# untitled.net
KiCad netlist of a schematic drawn in EAGLE
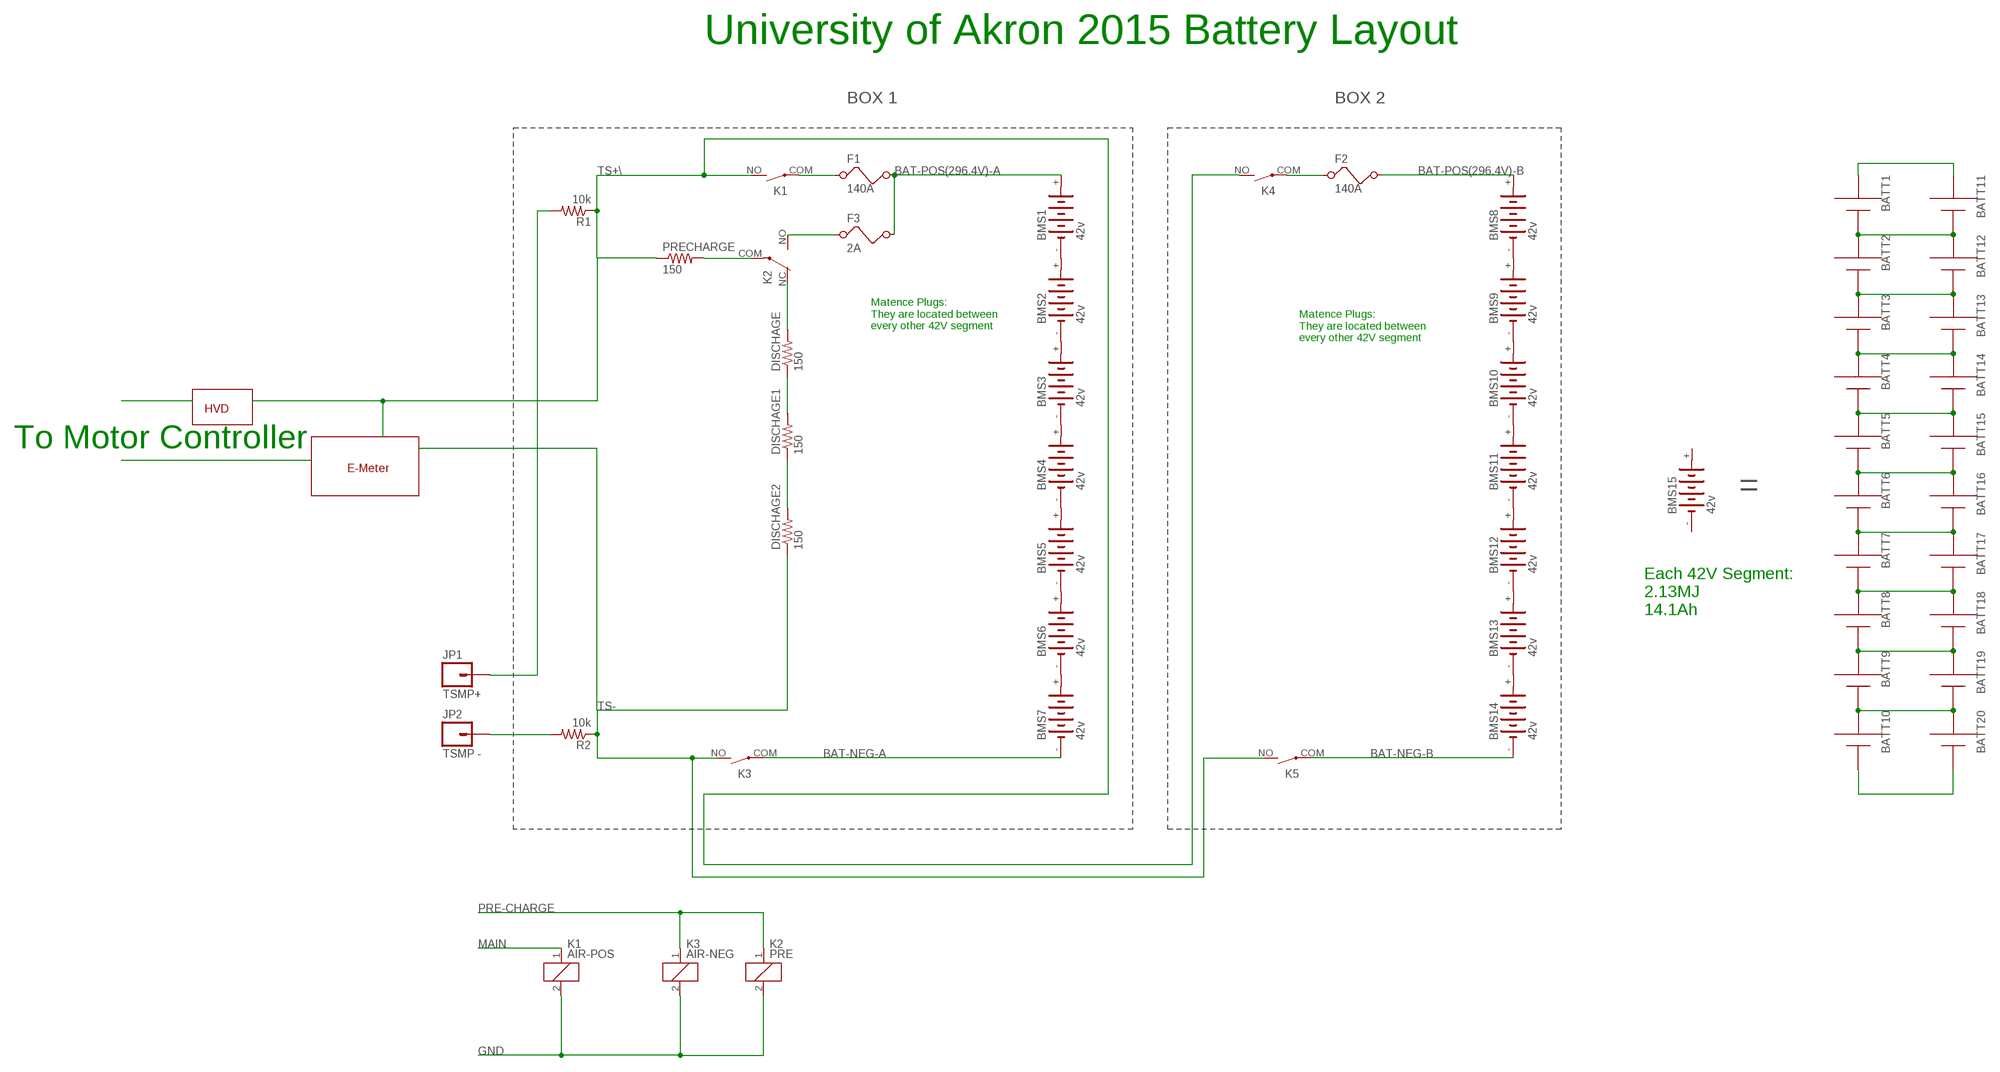
[diagram p0: schematic, sheet 1]
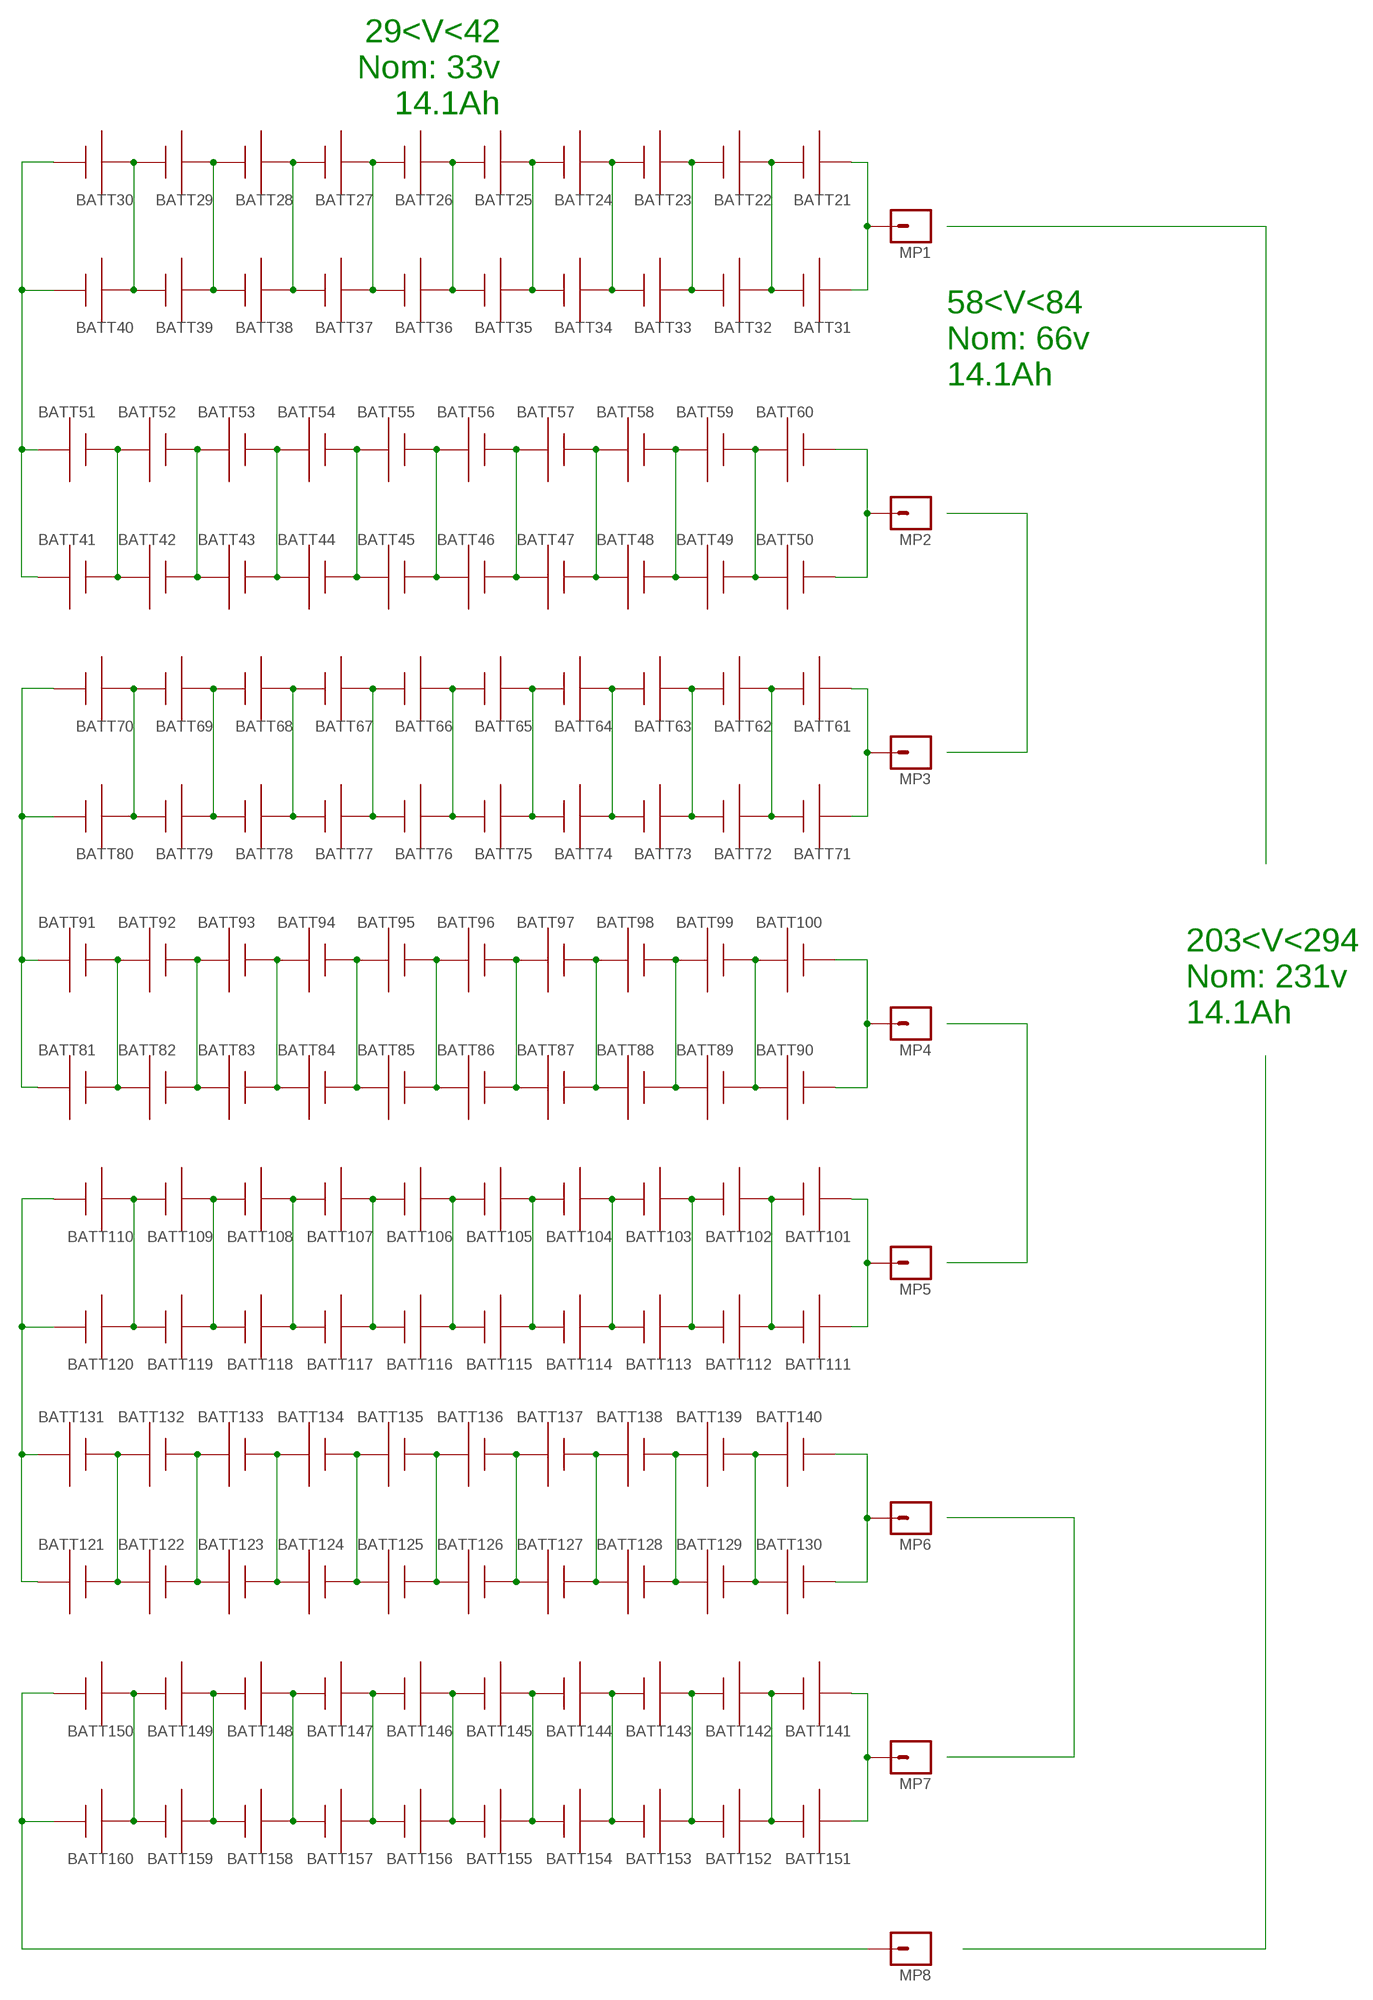
[diagram p1: schematic, sheet 2]
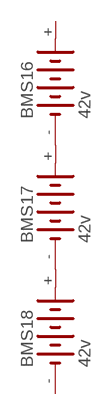
[diagram p2: schematic, sheet 3]

(export (version "E")
  (design (tool "Eeschema 10.0.6"))
  (components
    (comp (ref "BMS16")
      (value "42v")
      (footprint "eagle-import:VST4")
      (libsource (lib "eagle-import") (part "VST4V8"))
    )
    (comp (ref "BMS17")
      (value "42v")
      (footprint "eagle-import:VST4")
      (libsource (lib "eagle-import") (part "VST4V8"))
    )
    (comp (ref "BMS18")
      (value "42v")
      (footprint "eagle-import:VST4")
      (libsource (lib "eagle-import") (part "VST4V8"))
    )
    (comp (ref "BATT1")
      (value "AAA")
      (footprint "eagle-import:12BH412")
      (libsource (lib "eagle-import") (part "AAA"))
    )
    (comp (ref "BATT2")
      (value "AAA")
      (footprint "eagle-import:12BH412")
      (libsource (lib "eagle-import") (part "AAA"))
    )
    (comp (ref "BATT3")
      (value "AAA")
      (footprint "eagle-import:12BH412")
      (libsource (lib "eagle-import") (part "AAA"))
    )
    (comp (ref "BATT4")
      (value "AAA")
      (footprint "eagle-import:12BH412")
      (libsource (lib "eagle-import") (part "AAA"))
    )
    (comp (ref "BATT5")
      (value "AAA")
      (footprint "eagle-import:12BH412")
      (libsource (lib "eagle-import") (part "AAA"))
    )
    (comp (ref "BATT6")
      (value "AAA")
      (footprint "eagle-import:12BH412")
      (libsource (lib "eagle-import") (part "AAA"))
    )
    (comp (ref "BATT7")
      (value "AAA")
      (footprint "eagle-import:12BH412")
      (libsource (lib "eagle-import") (part "AAA"))
    )
    (comp (ref "BATT8")
      (value "AAA")
      (footprint "eagle-import:12BH412")
      (libsource (lib "eagle-import") (part "AAA"))
    )
    (comp (ref "BATT9")
      (value "AAA")
      (footprint "eagle-import:12BH412")
      (libsource (lib "eagle-import") (part "AAA"))
    )
    (comp (ref "BATT10")
      (value "AAA")
      (footprint "eagle-import:12BH412")
      (libsource (lib "eagle-import") (part "AAA"))
    )
    (comp (ref "BATT11")
      (value "AAA")
      (footprint "eagle-import:12BH412")
      (libsource (lib "eagle-import") (part "AAA"))
    )
    (comp (ref "BATT12")
      (value "AAA")
      (footprint "eagle-import:12BH412")
      (libsource (lib "eagle-import") (part "AAA"))
    )
    (comp (ref "BATT13")
      (value "AAA")
      (footprint "eagle-import:12BH412")
      (libsource (lib "eagle-import") (part "AAA"))
    )
    (comp (ref "BATT14")
      (value "AAA")
      (footprint "eagle-import:12BH412")
      (libsource (lib "eagle-import") (part "AAA"))
    )
    (comp (ref "BATT15")
      (value "AAA")
      (footprint "eagle-import:12BH412")
      (libsource (lib "eagle-import") (part "AAA"))
    )
    (comp (ref "BATT16")
      (value "AAA")
      (footprint "eagle-import:12BH412")
      (libsource (lib "eagle-import") (part "AAA"))
    )
    (comp (ref "BATT17")
      (value "AAA")
      (footprint "eagle-import:12BH412")
      (libsource (lib "eagle-import") (part "AAA"))
    )
    (comp (ref "BATT18")
      (value "AAA")
      (footprint "eagle-import:12BH412")
      (libsource (lib "eagle-import") (part "AAA"))
    )
    (comp (ref "BATT19")
      (value "AAA")
      (footprint "eagle-import:12BH412")
      (libsource (lib "eagle-import") (part "AAA"))
    )
    (comp (ref "BATT20")
      (value "AAA")
      (footprint "eagle-import:12BH412")
      (libsource (lib "eagle-import") (part "AAA"))
    )
    (comp (ref "BMS1")
      (value "42v")
      (footprint "eagle-import:VST4")
      (libsource (lib "eagle-import") (part "VST4V8"))
    )
    (comp (ref "BMS2")
      (value "42v")
      (footprint "eagle-import:VST4")
      (libsource (lib "eagle-import") (part "VST4V8"))
    )
    (comp (ref "BMS3")
      (value "42v")
      (footprint "eagle-import:VST4")
      (libsource (lib "eagle-import") (part "VST4V8"))
    )
    (comp (ref "BMS4")
      (value "42v")
      (footprint "eagle-import:VST4")
      (libsource (lib "eagle-import") (part "VST4V8"))
    )
    (comp (ref "BMS5")
      (value "42v")
      (footprint "eagle-import:VST4")
      (libsource (lib "eagle-import") (part "VST4V8"))
    )
    (comp (ref "BMS6")
      (value "42v")
      (footprint "eagle-import:VST4")
      (libsource (lib "eagle-import") (part "VST4V8"))
    )
    (comp (ref "BMS7")
      (value "42v")
      (footprint "eagle-import:VST4")
      (libsource (lib "eagle-import") (part "VST4V8"))
    )
    (comp (ref "BMS8")
      (value "42v")
      (footprint "eagle-import:VST4")
      (libsource (lib "eagle-import") (part "VST4V8"))
    )
    (comp (ref "BMS9")
      (value "42v")
      (footprint "eagle-import:VST4")
      (libsource (lib "eagle-import") (part "VST4V8"))
    )
    (comp (ref "BMS10")
      (value "42v")
      (footprint "eagle-import:VST4")
      (libsource (lib "eagle-import") (part "VST4V8"))
    )
    (comp (ref "BMS11")
      (value "42v")
      (footprint "eagle-import:VST4")
      (libsource (lib "eagle-import") (part "VST4V8"))
    )
    (comp (ref "BMS12")
      (value "42v")
      (footprint "eagle-import:VST4")
      (libsource (lib "eagle-import") (part "VST4V8"))
    )
    (comp (ref "BMS13")
      (value "42v")
      (footprint "eagle-import:VST4")
      (libsource (lib "eagle-import") (part "VST4V8"))
    )
    (comp (ref "BMS14")
      (value "42v")
      (footprint "eagle-import:VST4")
      (libsource (lib "eagle-import") (part "VST4V8"))
    )
    (comp (ref "BMS15")
      (value "42v")
      (footprint "eagle-import:VST4")
      (libsource (lib "eagle-import") (part "VST4V8"))
    )
    (comp (ref "DISCHAGE")
      (value "150")
      (footprint "eagle-import:0603-RES")
      (libsource (lib "eagle-import") (part "2.0KOHM1/10W5%(0603)"))
    )
    (comp (ref "DISCHAGE1")
      (value "150")
      (footprint "eagle-import:0603-RES")
      (libsource (lib "eagle-import") (part "2.0KOHM1/10W5%(0603)"))
    )
    (comp (ref "DISCHAGE2")
      (value "150")
      (footprint "eagle-import:0603-RES")
      (libsource (lib "eagle-import") (part "2.0KOHM1/10W5%(0603)"))
    )
    (comp (ref "F1")
      (value "140A")
      (footprint "eagle-import:FUSE")
      (libsource (lib "eagle-import") (part "FUSE"))
    )
    (comp (ref "F2")
      (value "140A")
      (footprint "eagle-import:FUSE")
      (libsource (lib "eagle-import") (part "FUSE"))
    )
    (comp (ref "F3")
      (value "2A")
      (footprint "eagle-import:FUSE")
      (libsource (lib "eagle-import") (part "FUSE"))
    )
    (comp (ref "JP1")
      (value "TSMP+")
      (footprint "eagle-import:SMTSO-256-ET")
      (libsource (lib "eagle-import") (part "M01-SMTSO-256-ET"))
    )
    (comp (ref "JP2")
      (value "TSMP -")
      (footprint "eagle-import:SMTSO-256-ET")
      (libsource (lib "eagle-import") (part "M01-SMTSO-256-ET"))
    )
    (comp (ref "K1")
      (value "AIR-POS")
      (footprint "eagle-import:APF30212A")
      (libsource (lib "eagle-import") (part "APF30212A"))
    )
    (comp (ref "K2")
      (value "PRE")
      (footprint "eagle-import:APF30212C")
      (libsource (lib "eagle-import") (part "APF30212C"))
    )
    (comp (ref "K3")
      (value "AIR-NEG")
      (footprint "eagle-import:APF30212A")
      (libsource (lib "eagle-import") (part "APF30212A"))
    )
    (comp (ref "K4")
      (value "AIR-POS")
      (footprint "eagle-import:APF30212A")
      (libsource (lib "eagle-import") (part "APF30212A"))
    )
    (comp (ref "K5")
      (value "AIR-NEG")
      (footprint "eagle-import:APF30212A")
      (libsource (lib "eagle-import") (part "APF30212A"))
    )
    (comp (ref "PRECHARGE")
      (value "150")
      (footprint "eagle-import:0603-RES")
      (libsource (lib "eagle-import") (part "2.0KOHM1/10W5%(0603)"))
    )
    (comp (ref "R1")
      (value "10k")
      (footprint "eagle-import:0805")
      (libsource (lib "eagle-import") (part "RESISTOR0805-RES"))
    )
    (comp (ref "R2")
      (value "10k")
      (footprint "eagle-import:0805")
      (libsource (lib "eagle-import") (part "RESISTOR0805-RES"))
    )
    (comp (ref "BATT21")
      (value "AAA")
      (footprint "eagle-import:12BH412")
      (libsource (lib "eagle-import") (part "AAA"))
    )
    (comp (ref "BATT22")
      (value "AAA")
      (footprint "eagle-import:12BH412")
      (libsource (lib "eagle-import") (part "AAA"))
    )
    (comp (ref "BATT23")
      (value "AAA")
      (footprint "eagle-import:12BH412")
      (libsource (lib "eagle-import") (part "AAA"))
    )
    (comp (ref "BATT24")
      (value "AAA")
      (footprint "eagle-import:12BH412")
      (libsource (lib "eagle-import") (part "AAA"))
    )
    (comp (ref "BATT25")
      (value "AAA")
      (footprint "eagle-import:12BH412")
      (libsource (lib "eagle-import") (part "AAA"))
    )
    (comp (ref "BATT26")
      (value "AAA")
      (footprint "eagle-import:12BH412")
      (libsource (lib "eagle-import") (part "AAA"))
    )
    (comp (ref "BATT27")
      (value "AAA")
      (footprint "eagle-import:12BH412")
      (libsource (lib "eagle-import") (part "AAA"))
    )
    (comp (ref "BATT28")
      (value "AAA")
      (footprint "eagle-import:12BH412")
      (libsource (lib "eagle-import") (part "AAA"))
    )
    (comp (ref "BATT29")
      (value "AAA")
      (footprint "eagle-import:12BH412")
      (libsource (lib "eagle-import") (part "AAA"))
    )
    (comp (ref "BATT30")
      (value "AAA")
      (footprint "eagle-import:12BH412")
      (libsource (lib "eagle-import") (part "AAA"))
    )
    (comp (ref "BATT31")
      (value "AAA")
      (footprint "eagle-import:12BH412")
      (libsource (lib "eagle-import") (part "AAA"))
    )
    (comp (ref "BATT32")
      (value "AAA")
      (footprint "eagle-import:12BH412")
      (libsource (lib "eagle-import") (part "AAA"))
    )
    (comp (ref "BATT33")
      (value "AAA")
      (footprint "eagle-import:12BH412")
      (libsource (lib "eagle-import") (part "AAA"))
    )
    (comp (ref "BATT34")
      (value "AAA")
      (footprint "eagle-import:12BH412")
      (libsource (lib "eagle-import") (part "AAA"))
    )
    (comp (ref "BATT35")
      (value "AAA")
      (footprint "eagle-import:12BH412")
      (libsource (lib "eagle-import") (part "AAA"))
    )
    (comp (ref "BATT36")
      (value "AAA")
      (footprint "eagle-import:12BH412")
      (libsource (lib "eagle-import") (part "AAA"))
    )
    (comp (ref "BATT37")
      (value "AAA")
      (footprint "eagle-import:12BH412")
      (libsource (lib "eagle-import") (part "AAA"))
    )
    (comp (ref "BATT38")
      (value "AAA")
      (footprint "eagle-import:12BH412")
      (libsource (lib "eagle-import") (part "AAA"))
    )
    (comp (ref "BATT39")
      (value "AAA")
      (footprint "eagle-import:12BH412")
      (libsource (lib "eagle-import") (part "AAA"))
    )
    (comp (ref "BATT40")
      (value "AAA")
      (footprint "eagle-import:12BH412")
      (libsource (lib "eagle-import") (part "AAA"))
    )
    (comp (ref "BATT41")
      (value "AAA")
      (footprint "eagle-import:12BH412")
      (libsource (lib "eagle-import") (part "AAA"))
    )
    (comp (ref "BATT42")
      (value "AAA")
      (footprint "eagle-import:12BH412")
      (libsource (lib "eagle-import") (part "AAA"))
    )
    (comp (ref "BATT43")
      (value "AAA")
      (footprint "eagle-import:12BH412")
      (libsource (lib "eagle-import") (part "AAA"))
    )
    (comp (ref "BATT44")
      (value "AAA")
      (footprint "eagle-import:12BH412")
      (libsource (lib "eagle-import") (part "AAA"))
    )
    (comp (ref "BATT45")
      (value "AAA")
      (footprint "eagle-import:12BH412")
      (libsource (lib "eagle-import") (part "AAA"))
    )
    (comp (ref "BATT46")
      (value "AAA")
      (footprint "eagle-import:12BH412")
      (libsource (lib "eagle-import") (part "AAA"))
    )
    (comp (ref "BATT47")
      (value "AAA")
      (footprint "eagle-import:12BH412")
      (libsource (lib "eagle-import") (part "AAA"))
    )
    (comp (ref "BATT48")
      (value "AAA")
      (footprint "eagle-import:12BH412")
      (libsource (lib "eagle-import") (part "AAA"))
    )
    (comp (ref "BATT49")
      (value "AAA")
      (footprint "eagle-import:12BH412")
      (libsource (lib "eagle-import") (part "AAA"))
    )
    (comp (ref "BATT50")
      (value "AAA")
      (footprint "eagle-import:12BH412")
      (libsource (lib "eagle-import") (part "AAA"))
    )
    (comp (ref "BATT51")
      (value "AAA")
      (footprint "eagle-import:12BH412")
      (libsource (lib "eagle-import") (part "AAA"))
    )
    (comp (ref "BATT52")
      (value "AAA")
      (footprint "eagle-import:12BH412")
      (libsource (lib "eagle-import") (part "AAA"))
    )
    (comp (ref "BATT53")
      (value "AAA")
      (footprint "eagle-import:12BH412")
      (libsource (lib "eagle-import") (part "AAA"))
    )
    (comp (ref "BATT54")
      (value "AAA")
      (footprint "eagle-import:12BH412")
      (libsource (lib "eagle-import") (part "AAA"))
    )
    (comp (ref "BATT55")
      (value "AAA")
      (footprint "eagle-import:12BH412")
      (libsource (lib "eagle-import") (part "AAA"))
    )
    (comp (ref "BATT56")
      (value "AAA")
      (footprint "eagle-import:12BH412")
      (libsource (lib "eagle-import") (part "AAA"))
    )
    (comp (ref "BATT57")
      (value "AAA")
      (footprint "eagle-import:12BH412")
      (libsource (lib "eagle-import") (part "AAA"))
    )
    (comp (ref "BATT58")
      (value "AAA")
      (footprint "eagle-import:12BH412")
      (libsource (lib "eagle-import") (part "AAA"))
    )
    (comp (ref "BATT59")
      (value "AAA")
      (footprint "eagle-import:12BH412")
      (libsource (lib "eagle-import") (part "AAA"))
    )
    (comp (ref "BATT60")
      (value "AAA")
      (footprint "eagle-import:12BH412")
      (libsource (lib "eagle-import") (part "AAA"))
    )
    (comp (ref "BATT61")
      (value "AAA")
      (footprint "eagle-import:12BH412")
      (libsource (lib "eagle-import") (part "AAA"))
    )
    (comp (ref "BATT62")
      (value "AAA")
      (footprint "eagle-import:12BH412")
      (libsource (lib "eagle-import") (part "AAA"))
    )
    (comp (ref "BATT63")
      (value "AAA")
      (footprint "eagle-import:12BH412")
      (libsource (lib "eagle-import") (part "AAA"))
    )
    (comp (ref "BATT64")
      (value "AAA")
      (footprint "eagle-import:12BH412")
      (libsource (lib "eagle-import") (part "AAA"))
    )
    (comp (ref "BATT65")
      (value "AAA")
      (footprint "eagle-import:12BH412")
      (libsource (lib "eagle-import") (part "AAA"))
    )
    (comp (ref "BATT66")
      (value "AAA")
      (footprint "eagle-import:12BH412")
      (libsource (lib "eagle-import") (part "AAA"))
    )
    (comp (ref "BATT67")
      (value "AAA")
      (footprint "eagle-import:12BH412")
      (libsource (lib "eagle-import") (part "AAA"))
    )
    (comp (ref "BATT68")
      (value "AAA")
      (footprint "eagle-import:12BH412")
      (libsource (lib "eagle-import") (part "AAA"))
    )
    (comp (ref "BATT69")
      (value "AAA")
      (footprint "eagle-import:12BH412")
      (libsource (lib "eagle-import") (part "AAA"))
    )
    (comp (ref "BATT70")
      (value "AAA")
      (footprint "eagle-import:12BH412")
      (libsource (lib "eagle-import") (part "AAA"))
    )
    (comp (ref "BATT71")
      (value "AAA")
      (footprint "eagle-import:12BH412")
      (libsource (lib "eagle-import") (part "AAA"))
    )
    (comp (ref "BATT72")
      (value "AAA")
      (footprint "eagle-import:12BH412")
      (libsource (lib "eagle-import") (part "AAA"))
    )
    (comp (ref "BATT73")
      (value "AAA")
      (footprint "eagle-import:12BH412")
      (libsource (lib "eagle-import") (part "AAA"))
    )
    (comp (ref "BATT74")
      (value "AAA")
      (footprint "eagle-import:12BH412")
      (libsource (lib "eagle-import") (part "AAA"))
    )
    (comp (ref "BATT75")
      (value "AAA")
      (footprint "eagle-import:12BH412")
      (libsource (lib "eagle-import") (part "AAA"))
    )
    (comp (ref "BATT76")
      (value "AAA")
      (footprint "eagle-import:12BH412")
      (libsource (lib "eagle-import") (part "AAA"))
    )
    (comp (ref "BATT77")
      (value "AAA")
      (footprint "eagle-import:12BH412")
      (libsource (lib "eagle-import") (part "AAA"))
    )
    (comp (ref "BATT78")
      (value "AAA")
      (footprint "eagle-import:12BH412")
      (libsource (lib "eagle-import") (part "AAA"))
    )
    (comp (ref "BATT79")
      (value "AAA")
      (footprint "eagle-import:12BH412")
      (libsource (lib "eagle-import") (part "AAA"))
    )
    (comp (ref "BATT80")
      (value "AAA")
      (footprint "eagle-import:12BH412")
      (libsource (lib "eagle-import") (part "AAA"))
    )
    (comp (ref "BATT81")
      (value "AAA")
      (footprint "eagle-import:12BH412")
      (libsource (lib "eagle-import") (part "AAA"))
    )
    (comp (ref "BATT82")
      (value "AAA")
      (footprint "eagle-import:12BH412")
      (libsource (lib "eagle-import") (part "AAA"))
    )
    (comp (ref "BATT83")
      (value "AAA")
      (footprint "eagle-import:12BH412")
      (libsource (lib "eagle-import") (part "AAA"))
    )
    (comp (ref "BATT84")
      (value "AAA")
      (footprint "eagle-import:12BH412")
      (libsource (lib "eagle-import") (part "AAA"))
    )
    (comp (ref "BATT85")
      (value "AAA")
      (footprint "eagle-import:12BH412")
      (libsource (lib "eagle-import") (part "AAA"))
    )
    (comp (ref "BATT86")
      (value "AAA")
      (footprint "eagle-import:12BH412")
      (libsource (lib "eagle-import") (part "AAA"))
    )
    (comp (ref "BATT87")
      (value "AAA")
      (footprint "eagle-import:12BH412")
      (libsource (lib "eagle-import") (part "AAA"))
    )
    (comp (ref "BATT88")
      (value "AAA")
      (footprint "eagle-import:12BH412")
      (libsource (lib "eagle-import") (part "AAA"))
    )
    (comp (ref "BATT89")
      (value "AAA")
      (footprint "eagle-import:12BH412")
      (libsource (lib "eagle-import") (part "AAA"))
    )
    (comp (ref "BATT90")
      (value "AAA")
      (footprint "eagle-import:12BH412")
      (libsource (lib "eagle-import") (part "AAA"))
    )
    (comp (ref "BATT91")
      (value "AAA")
      (footprint "eagle-import:12BH412")
      (libsource (lib "eagle-import") (part "AAA"))
    )
    (comp (ref "BATT92")
      (value "AAA")
      (footprint "eagle-import:12BH412")
      (libsource (lib "eagle-import") (part "AAA"))
    )
    (comp (ref "BATT93")
      (value "AAA")
      (footprint "eagle-import:12BH412")
      (libsource (lib "eagle-import") (part "AAA"))
    )
    (comp (ref "BATT94")
      (value "AAA")
      (footprint "eagle-import:12BH412")
      (libsource (lib "eagle-import") (part "AAA"))
    )
    (comp (ref "BATT95")
      (value "AAA")
      (footprint "eagle-import:12BH412")
      (libsource (lib "eagle-import") (part "AAA"))
    )
    (comp (ref "BATT96")
      (value "AAA")
      (footprint "eagle-import:12BH412")
      (libsource (lib "eagle-import") (part "AAA"))
    )
    (comp (ref "BATT97")
      (value "AAA")
      (footprint "eagle-import:12BH412")
      (libsource (lib "eagle-import") (part "AAA"))
    )
    (comp (ref "BATT98")
      (value "AAA")
      (footprint "eagle-import:12BH412")
      (libsource (lib "eagle-import") (part "AAA"))
    )
    (comp (ref "BATT99")
      (value "AAA")
      (footprint "eagle-import:12BH412")
      (libsource (lib "eagle-import") (part "AAA"))
    )
    (comp (ref "BATT100")
      (value "AAA")
      (footprint "eagle-import:12BH412")
      (libsource (lib "eagle-import") (part "AAA"))
    )
    (comp (ref "BATT101")
      (value "AAA")
      (footprint "eagle-import:12BH412")
      (libsource (lib "eagle-import") (part "AAA"))
    )
    (comp (ref "BATT102")
      (value "AAA")
      (footprint "eagle-import:12BH412")
      (libsource (lib "eagle-import") (part "AAA"))
    )
    (comp (ref "BATT103")
      (value "AAA")
      (footprint "eagle-import:12BH412")
      (libsource (lib "eagle-import") (part "AAA"))
    )
    (comp (ref "BATT104")
      (value "AAA")
      (footprint "eagle-import:12BH412")
      (libsource (lib "eagle-import") (part "AAA"))
    )
    (comp (ref "BATT105")
      (value "AAA")
      (footprint "eagle-import:12BH412")
      (libsource (lib "eagle-import") (part "AAA"))
    )
    (comp (ref "BATT106")
      (value "AAA")
      (footprint "eagle-import:12BH412")
      (libsource (lib "eagle-import") (part "AAA"))
    )
    (comp (ref "BATT107")
      (value "AAA")
      (footprint "eagle-import:12BH412")
      (libsource (lib "eagle-import") (part "AAA"))
    )
    (comp (ref "BATT108")
      (value "AAA")
      (footprint "eagle-import:12BH412")
      (libsource (lib "eagle-import") (part "AAA"))
    )
    (comp (ref "BATT109")
      (value "AAA")
      (footprint "eagle-import:12BH412")
      (libsource (lib "eagle-import") (part "AAA"))
    )
    (comp (ref "BATT110")
      (value "AAA")
      (footprint "eagle-import:12BH412")
      (libsource (lib "eagle-import") (part "AAA"))
    )
    (comp (ref "BATT111")
      (value "AAA")
      (footprint "eagle-import:12BH412")
      (libsource (lib "eagle-import") (part "AAA"))
    )
    (comp (ref "BATT112")
      (value "AAA")
      (footprint "eagle-import:12BH412")
      (libsource (lib "eagle-import") (part "AAA"))
    )
    (comp (ref "BATT113")
      (value "AAA")
      (footprint "eagle-import:12BH412")
      (libsource (lib "eagle-import") (part "AAA"))
    )
    (comp (ref "BATT114")
      (value "AAA")
      (footprint "eagle-import:12BH412")
      (libsource (lib "eagle-import") (part "AAA"))
    )
    (comp (ref "BATT115")
      (value "AAA")
      (footprint "eagle-import:12BH412")
      (libsource (lib "eagle-import") (part "AAA"))
    )
    (comp (ref "BATT116")
      (value "AAA")
      (footprint "eagle-import:12BH412")
      (libsource (lib "eagle-import") (part "AAA"))
    )
    (comp (ref "BATT117")
      (value "AAA")
      (footprint "eagle-import:12BH412")
      (libsource (lib "eagle-import") (part "AAA"))
    )
    (comp (ref "BATT118")
      (value "AAA")
      (footprint "eagle-import:12BH412")
      (libsource (lib "eagle-import") (part "AAA"))
    )
    (comp (ref "BATT119")
      (value "AAA")
      (footprint "eagle-import:12BH412")
      (libsource (lib "eagle-import") (part "AAA"))
    )
    (comp (ref "BATT120")
      (value "AAA")
      (footprint "eagle-import:12BH412")
      (libsource (lib "eagle-import") (part "AAA"))
    )
    (comp (ref "BATT121")
      (value "AAA")
      (footprint "eagle-import:12BH412")
      (libsource (lib "eagle-import") (part "AAA"))
    )
    (comp (ref "BATT122")
      (value "AAA")
      (footprint "eagle-import:12BH412")
      (libsource (lib "eagle-import") (part "AAA"))
    )
    (comp (ref "BATT123")
      (value "AAA")
      (footprint "eagle-import:12BH412")
      (libsource (lib "eagle-import") (part "AAA"))
    )
    (comp (ref "BATT124")
      (value "AAA")
      (footprint "eagle-import:12BH412")
      (libsource (lib "eagle-import") (part "AAA"))
    )
    (comp (ref "BATT125")
      (value "AAA")
      (footprint "eagle-import:12BH412")
      (libsource (lib "eagle-import") (part "AAA"))
    )
    (comp (ref "BATT126")
      (value "AAA")
      (footprint "eagle-import:12BH412")
      (libsource (lib "eagle-import") (part "AAA"))
    )
    (comp (ref "BATT127")
      (value "AAA")
      (footprint "eagle-import:12BH412")
      (libsource (lib "eagle-import") (part "AAA"))
    )
    (comp (ref "BATT128")
      (value "AAA")
      (footprint "eagle-import:12BH412")
      (libsource (lib "eagle-import") (part "AAA"))
    )
    (comp (ref "BATT129")
      (value "AAA")
      (footprint "eagle-import:12BH412")
      (libsource (lib "eagle-import") (part "AAA"))
    )
    (comp (ref "BATT130")
      (value "AAA")
      (footprint "eagle-import:12BH412")
      (libsource (lib "eagle-import") (part "AAA"))
    )
    (comp (ref "BATT131")
      (value "AAA")
      (footprint "eagle-import:12BH412")
      (libsource (lib "eagle-import") (part "AAA"))
    )
    (comp (ref "BATT132")
      (value "AAA")
      (footprint "eagle-import:12BH412")
      (libsource (lib "eagle-import") (part "AAA"))
    )
    (comp (ref "BATT133")
      (value "AAA")
      (footprint "eagle-import:12BH412")
      (libsource (lib "eagle-import") (part "AAA"))
    )
    (comp (ref "BATT134")
      (value "AAA")
      (footprint "eagle-import:12BH412")
      (libsource (lib "eagle-import") (part "AAA"))
    )
    (comp (ref "BATT135")
      (value "AAA")
      (footprint "eagle-import:12BH412")
      (libsource (lib "eagle-import") (part "AAA"))
    )
    (comp (ref "BATT136")
      (value "AAA")
      (footprint "eagle-import:12BH412")
      (libsource (lib "eagle-import") (part "AAA"))
    )
    (comp (ref "BATT137")
      (value "AAA")
      (footprint "eagle-import:12BH412")
      (libsource (lib "eagle-import") (part "AAA"))
    )
    (comp (ref "BATT138")
      (value "AAA")
      (footprint "eagle-import:12BH412")
      (libsource (lib "eagle-import") (part "AAA"))
    )
    (comp (ref "BATT139")
      (value "AAA")
      (footprint "eagle-import:12BH412")
      (libsource (lib "eagle-import") (part "AAA"))
    )
    (comp (ref "BATT140")
      (value "AAA")
      (footprint "eagle-import:12BH412")
      (libsource (lib "eagle-import") (part "AAA"))
    )
    (comp (ref "BATT141")
      (value "AAA")
      (footprint "eagle-import:12BH412")
      (libsource (lib "eagle-import") (part "AAA"))
    )
    (comp (ref "BATT142")
      (value "AAA")
      (footprint "eagle-import:12BH412")
      (libsource (lib "eagle-import") (part "AAA"))
    )
    (comp (ref "BATT143")
      (value "AAA")
      (footprint "eagle-import:12BH412")
      (libsource (lib "eagle-import") (part "AAA"))
    )
    (comp (ref "BATT144")
      (value "AAA")
      (footprint "eagle-import:12BH412")
      (libsource (lib "eagle-import") (part "AAA"))
    )
    (comp (ref "BATT145")
      (value "AAA")
      (footprint "eagle-import:12BH412")
      (libsource (lib "eagle-import") (part "AAA"))
    )
    (comp (ref "BATT146")
      (value "AAA")
      (footprint "eagle-import:12BH412")
      (libsource (lib "eagle-import") (part "AAA"))
    )
    (comp (ref "BATT147")
      (value "AAA")
      (footprint "eagle-import:12BH412")
      (libsource (lib "eagle-import") (part "AAA"))
    )
    (comp (ref "BATT148")
      (value "AAA")
      (footprint "eagle-import:12BH412")
      (libsource (lib "eagle-import") (part "AAA"))
    )
    (comp (ref "BATT149")
      (value "AAA")
      (footprint "eagle-import:12BH412")
      (libsource (lib "eagle-import") (part "AAA"))
    )
    (comp (ref "BATT150")
      (value "AAA")
      (footprint "eagle-import:12BH412")
      (libsource (lib "eagle-import") (part "AAA"))
    )
    (comp (ref "BATT151")
      (value "AAA")
      (footprint "eagle-import:12BH412")
      (libsource (lib "eagle-import") (part "AAA"))
    )
    (comp (ref "BATT152")
      (value "AAA")
      (footprint "eagle-import:12BH412")
      (libsource (lib "eagle-import") (part "AAA"))
    )
    (comp (ref "BATT153")
      (value "AAA")
      (footprint "eagle-import:12BH412")
      (libsource (lib "eagle-import") (part "AAA"))
    )
    (comp (ref "BATT154")
      (value "AAA")
      (footprint "eagle-import:12BH412")
      (libsource (lib "eagle-import") (part "AAA"))
    )
    (comp (ref "BATT155")
      (value "AAA")
      (footprint "eagle-import:12BH412")
      (libsource (lib "eagle-import") (part "AAA"))
    )
    (comp (ref "BATT156")
      (value "AAA")
      (footprint "eagle-import:12BH412")
      (libsource (lib "eagle-import") (part "AAA"))
    )
    (comp (ref "BATT157")
      (value "AAA")
      (footprint "eagle-import:12BH412")
      (libsource (lib "eagle-import") (part "AAA"))
    )
    (comp (ref "BATT158")
      (value "AAA")
      (footprint "eagle-import:12BH412")
      (libsource (lib "eagle-import") (part "AAA"))
    )
    (comp (ref "BATT159")
      (value "AAA")
      (footprint "eagle-import:12BH412")
      (libsource (lib "eagle-import") (part "AAA"))
    )
    (comp (ref "BATT160")
      (value "AAA")
      (footprint "eagle-import:12BH412")
      (libsource (lib "eagle-import") (part "AAA"))
    )
    (comp (ref "MP1")
      (value "M01POGOPIN_HOLE_0.58")
      (footprint "eagle-import:1X01_POGOPIN_HOLE_0.58")
      (libsource (lib "eagle-import") (part "M01POGOPIN_HOLE_0.58"))
    )
    (comp (ref "MP2")
      (value "M01POGOPIN_HOLE_0.58")
      (footprint "eagle-import:1X01_POGOPIN_HOLE_0.58")
      (libsource (lib "eagle-import") (part "M01POGOPIN_HOLE_0.58"))
    )
    (comp (ref "MP3")
      (value "M01POGOPIN_HOLE_0.58")
      (footprint "eagle-import:1X01_POGOPIN_HOLE_0.58")
      (libsource (lib "eagle-import") (part "M01POGOPIN_HOLE_0.58"))
    )
    (comp (ref "MP4")
      (value "M01POGOPIN_HOLE_0.58")
      (footprint "eagle-import:1X01_POGOPIN_HOLE_0.58")
      (libsource (lib "eagle-import") (part "M01POGOPIN_HOLE_0.58"))
    )
    (comp (ref "MP5")
      (value "M01POGOPIN_HOLE_0.58")
      (footprint "eagle-import:1X01_POGOPIN_HOLE_0.58")
      (libsource (lib "eagle-import") (part "M01POGOPIN_HOLE_0.58"))
    )
    (comp (ref "MP6")
      (value "M01POGOPIN_HOLE_0.58")
      (footprint "eagle-import:1X01_POGOPIN_HOLE_0.58")
      (libsource (lib "eagle-import") (part "M01POGOPIN_HOLE_0.58"))
    )
    (comp (ref "MP7")
      (value "M01POGOPIN_HOLE_0.58")
      (footprint "eagle-import:1X01_POGOPIN_HOLE_0.58")
      (libsource (lib "eagle-import") (part "M01POGOPIN_HOLE_0.58"))
    )
    (comp (ref "MP8")
      (value "M01POGOPIN_HOLE_0.58")
      (footprint "eagle-import:1X01_POGOPIN_HOLE_0.58")
      (libsource (lib "eagle-import") (part "M01POGOPIN_HOLE_0.58"))
    )
  )
  (nets
    (net (code "1") (name "BAT-NEG-A") (class "Default")
      (node (ref "BMS7") (pin "-") (pinfunction "-_-") (pintype "passive"))
      (node (ref "K3") (pin "COM") (pinfunction "P_COM") (pintype "passive"))
    )
    (net (code "2") (name "BAT-NEG-B") (class "Default")
      (node (ref "BMS14") (pin "-") (pinfunction "-_-") (pintype "passive"))
      (node (ref "K5") (pin "COM") (pinfunction "P_COM") (pintype "passive"))
    )
    (net (code "3") (name "BAT-POS(296.4V)-A") (class "Default")
      (node (ref "BMS1") (pin "+") (pinfunction "+_+") (pintype "passive"))
      (node (ref "F1") (pin "2") (pinfunction "2_2") (pintype "passive"))
      (node (ref "F3") (pin "2") (pinfunction "2_2") (pintype "passive"))
    )
    (net (code "4") (name "BAT-POS(296.4V)-B") (class "Default")
      (node (ref "BMS8") (pin "+") (pinfunction "+_+") (pintype "passive"))
      (node (ref "F2") (pin "2") (pinfunction "2_2") (pintype "passive"))
    )
    (net (code "5") (name "GND") (class "Default")
      (node (ref "K1") (pin "2") (pinfunction "2_2") (pintype "passive"))
      (node (ref "K2") (pin "2") (pinfunction "2_2") (pintype "passive"))
      (node (ref "K3") (pin "2") (pinfunction "2_2") (pintype "passive"))
    )
    (net (code "6") (name "MAIN") (class "Default")
      (node (ref "K1") (pin "1") (pinfunction "1_1") (pintype "passive"))
    )
    (net (code "7") (name "Net-(BATT1-Pad+)") (class "Default")
      (node (ref "BATT1") (pin "+") (pinfunction "+_+") (pintype "bidirectional"))
      (node (ref "BATT11") (pin "+") (pinfunction "+_+") (pintype "bidirectional"))
      (node (ref "BATT12") (pin "-") (pinfunction "-_-") (pintype "bidirectional"))
      (node (ref "BATT2") (pin "-") (pinfunction "-_-") (pintype "bidirectional"))
    )
    (net (code "8") (name "Net-(BATT1-Pad-)") (class "Default")
      (node (ref "BATT1") (pin "-") (pinfunction "-_-") (pintype "bidirectional"))
      (node (ref "BATT11") (pin "-") (pinfunction "-_-") (pintype "bidirectional"))
    )
    (net (code "9") (name "Net-(BATT10-Pad+)") (class "Default")
      (node (ref "BATT10") (pin "+") (pinfunction "+_+") (pintype "bidirectional"))
      (node (ref "BATT20") (pin "+") (pinfunction "+_+") (pintype "bidirectional"))
    )
    (net (code "10") (name "Net-(BATT10-Pad-)") (class "Default")
      (node (ref "BATT10") (pin "-") (pinfunction "-_-") (pintype "bidirectional"))
      (node (ref "BATT19") (pin "+") (pinfunction "+_+") (pintype "bidirectional"))
      (node (ref "BATT20") (pin "-") (pinfunction "-_-") (pintype "bidirectional"))
      (node (ref "BATT9") (pin "+") (pinfunction "+_+") (pintype "bidirectional"))
    )
    (net (code "11") (name "Net-(BATT12-Pad+)") (class "Default")
      (node (ref "BATT12") (pin "+") (pinfunction "+_+") (pintype "bidirectional"))
      (node (ref "BATT13") (pin "-") (pinfunction "-_-") (pintype "bidirectional"))
      (node (ref "BATT2") (pin "+") (pinfunction "+_+") (pintype "bidirectional"))
      (node (ref "BATT3") (pin "-") (pinfunction "-_-") (pintype "bidirectional"))
    )
    (net (code "12") (name "Net-(BATT13-Pad+)") (class "Default")
      (node (ref "BATT13") (pin "+") (pinfunction "+_+") (pintype "bidirectional"))
      (node (ref "BATT14") (pin "-") (pinfunction "-_-") (pintype "bidirectional"))
      (node (ref "BATT3") (pin "+") (pinfunction "+_+") (pintype "bidirectional"))
      (node (ref "BATT4") (pin "-") (pinfunction "-_-") (pintype "bidirectional"))
    )
    (net (code "13") (name "Net-(BATT14-Pad+)") (class "Default")
      (node (ref "BATT14") (pin "+") (pinfunction "+_+") (pintype "bidirectional"))
      (node (ref "BATT15") (pin "-") (pinfunction "-_-") (pintype "bidirectional"))
      (node (ref "BATT4") (pin "+") (pinfunction "+_+") (pintype "bidirectional"))
      (node (ref "BATT5") (pin "-") (pinfunction "-_-") (pintype "bidirectional"))
    )
    (net (code "14") (name "Net-(BATT15-Pad+)") (class "Default")
      (node (ref "BATT15") (pin "+") (pinfunction "+_+") (pintype "bidirectional"))
      (node (ref "BATT16") (pin "-") (pinfunction "-_-") (pintype "bidirectional"))
      (node (ref "BATT5") (pin "+") (pinfunction "+_+") (pintype "bidirectional"))
      (node (ref "BATT6") (pin "-") (pinfunction "-_-") (pintype "bidirectional"))
    )
    (net (code "15") (name "Net-(BATT16-Pad+)") (class "Default")
      (node (ref "BATT16") (pin "+") (pinfunction "+_+") (pintype "bidirectional"))
      (node (ref "BATT17") (pin "-") (pinfunction "-_-") (pintype "bidirectional"))
      (node (ref "BATT6") (pin "+") (pinfunction "+_+") (pintype "bidirectional"))
      (node (ref "BATT7") (pin "-") (pinfunction "-_-") (pintype "bidirectional"))
    )
    (net (code "16") (name "Net-(BATT17-Pad+)") (class "Default")
      (node (ref "BATT17") (pin "+") (pinfunction "+_+") (pintype "bidirectional"))
      (node (ref "BATT18") (pin "-") (pinfunction "-_-") (pintype "bidirectional"))
      (node (ref "BATT7") (pin "+") (pinfunction "+_+") (pintype "bidirectional"))
      (node (ref "BATT8") (pin "-") (pinfunction "-_-") (pintype "bidirectional"))
    )
    (net (code "17") (name "Net-(BATT18-Pad+)") (class "Default")
      (node (ref "BATT18") (pin "+") (pinfunction "+_+") (pintype "bidirectional"))
      (node (ref "BATT19") (pin "-") (pinfunction "-_-") (pintype "bidirectional"))
      (node (ref "BATT8") (pin "+") (pinfunction "+_+") (pintype "bidirectional"))
      (node (ref "BATT9") (pin "-") (pinfunction "-_-") (pintype "bidirectional"))
    )
    (net (code "18") (name "Net-(BATT21-Pad+)") (class "Default")
      (node (ref "BATT21") (pin "+") (pinfunction "+_+") (pintype "bidirectional"))
      (node (ref "BATT22") (pin "-") (pinfunction "-_-") (pintype "bidirectional"))
      (node (ref "BATT31") (pin "+") (pinfunction "+_+") (pintype "bidirectional"))
      (node (ref "BATT32") (pin "-") (pinfunction "-_-") (pintype "bidirectional"))
    )
    (net (code "19") (name "Net-(BATT21-Pad-)") (class "Default")
      (node (ref "BATT21") (pin "-") (pinfunction "-_-") (pintype "bidirectional"))
      (node (ref "BATT31") (pin "-") (pinfunction "-_-") (pintype "bidirectional"))
      (node (ref "MP1") (pin "1") (pinfunction "1_1") (pintype "passive"))
    )
    (net (code "20") (name "Net-(BATT22-Pad+)") (class "Default")
      (node (ref "BATT22") (pin "+") (pinfunction "+_+") (pintype "bidirectional"))
      (node (ref "BATT23") (pin "-") (pinfunction "-_-") (pintype "bidirectional"))
      (node (ref "BATT32") (pin "+") (pinfunction "+_+") (pintype "bidirectional"))
      (node (ref "BATT33") (pin "-") (pinfunction "-_-") (pintype "bidirectional"))
    )
    (net (code "21") (name "Net-(BATT23-Pad+)") (class "Default")
      (node (ref "BATT23") (pin "+") (pinfunction "+_+") (pintype "bidirectional"))
      (node (ref "BATT24") (pin "-") (pinfunction "-_-") (pintype "bidirectional"))
      (node (ref "BATT33") (pin "+") (pinfunction "+_+") (pintype "bidirectional"))
      (node (ref "BATT34") (pin "-") (pinfunction "-_-") (pintype "bidirectional"))
    )
    (net (code "22") (name "Net-(BATT24-Pad+)") (class "Default")
      (node (ref "BATT24") (pin "+") (pinfunction "+_+") (pintype "bidirectional"))
      (node (ref "BATT25") (pin "-") (pinfunction "-_-") (pintype "bidirectional"))
      (node (ref "BATT34") (pin "+") (pinfunction "+_+") (pintype "bidirectional"))
      (node (ref "BATT35") (pin "-") (pinfunction "-_-") (pintype "bidirectional"))
    )
    (net (code "23") (name "Net-(BATT25-Pad+)") (class "Default")
      (node (ref "BATT25") (pin "+") (pinfunction "+_+") (pintype "bidirectional"))
      (node (ref "BATT26") (pin "-") (pinfunction "-_-") (pintype "bidirectional"))
      (node (ref "BATT35") (pin "+") (pinfunction "+_+") (pintype "bidirectional"))
      (node (ref "BATT36") (pin "-") (pinfunction "-_-") (pintype "bidirectional"))
    )
    (net (code "24") (name "Net-(BATT26-Pad+)") (class "Default")
      (node (ref "BATT26") (pin "+") (pinfunction "+_+") (pintype "bidirectional"))
      (node (ref "BATT27") (pin "-") (pinfunction "-_-") (pintype "bidirectional"))
      (node (ref "BATT36") (pin "+") (pinfunction "+_+") (pintype "bidirectional"))
      (node (ref "BATT37") (pin "-") (pinfunction "-_-") (pintype "bidirectional"))
    )
    (net (code "25") (name "Net-(BATT27-Pad+)") (class "Default")
      (node (ref "BATT27") (pin "+") (pinfunction "+_+") (pintype "bidirectional"))
      (node (ref "BATT28") (pin "-") (pinfunction "-_-") (pintype "bidirectional"))
      (node (ref "BATT37") (pin "+") (pinfunction "+_+") (pintype "bidirectional"))
      (node (ref "BATT38") (pin "-") (pinfunction "-_-") (pintype "bidirectional"))
    )
    (net (code "26") (name "Net-(BATT28-Pad+)") (class "Default")
      (node (ref "BATT28") (pin "+") (pinfunction "+_+") (pintype "bidirectional"))
      (node (ref "BATT29") (pin "-") (pinfunction "-_-") (pintype "bidirectional"))
      (node (ref "BATT38") (pin "+") (pinfunction "+_+") (pintype "bidirectional"))
      (node (ref "BATT39") (pin "-") (pinfunction "-_-") (pintype "bidirectional"))
    )
    (net (code "27") (name "Net-(BATT29-Pad+)") (class "Default")
      (node (ref "BATT29") (pin "+") (pinfunction "+_+") (pintype "bidirectional"))
      (node (ref "BATT30") (pin "-") (pinfunction "-_-") (pintype "bidirectional"))
      (node (ref "BATT39") (pin "+") (pinfunction "+_+") (pintype "bidirectional"))
      (node (ref "BATT40") (pin "-") (pinfunction "-_-") (pintype "bidirectional"))
    )
    (net (code "28") (name "Net-(BATT30-Pad+)") (class "Default")
      (node (ref "BATT30") (pin "+") (pinfunction "+_+") (pintype "bidirectional"))
      (node (ref "BATT40") (pin "+") (pinfunction "+_+") (pintype "bidirectional"))
      (node (ref "BATT41") (pin "-") (pinfunction "-_-") (pintype "bidirectional"))
      (node (ref "BATT51") (pin "-") (pinfunction "-_-") (pintype "bidirectional"))
    )
    (net (code "29") (name "Net-(BATT41-Pad+)") (class "Default")
      (node (ref "BATT41") (pin "+") (pinfunction "+_+") (pintype "bidirectional"))
      (node (ref "BATT42") (pin "-") (pinfunction "-_-") (pintype "bidirectional"))
      (node (ref "BATT51") (pin "+") (pinfunction "+_+") (pintype "bidirectional"))
      (node (ref "BATT52") (pin "-") (pinfunction "-_-") (pintype "bidirectional"))
    )
    (net (code "30") (name "Net-(BATT42-Pad+)") (class "Default")
      (node (ref "BATT42") (pin "+") (pinfunction "+_+") (pintype "bidirectional"))
      (node (ref "BATT43") (pin "-") (pinfunction "-_-") (pintype "bidirectional"))
      (node (ref "BATT52") (pin "+") (pinfunction "+_+") (pintype "bidirectional"))
      (node (ref "BATT53") (pin "-") (pinfunction "-_-") (pintype "bidirectional"))
    )
    (net (code "31") (name "Net-(BATT43-Pad+)") (class "Default")
      (node (ref "BATT43") (pin "+") (pinfunction "+_+") (pintype "bidirectional"))
      (node (ref "BATT44") (pin "-") (pinfunction "-_-") (pintype "bidirectional"))
      (node (ref "BATT53") (pin "+") (pinfunction "+_+") (pintype "bidirectional"))
      (node (ref "BATT54") (pin "-") (pinfunction "-_-") (pintype "bidirectional"))
    )
    (net (code "32") (name "Net-(BATT44-Pad+)") (class "Default")
      (node (ref "BATT44") (pin "+") (pinfunction "+_+") (pintype "bidirectional"))
      (node (ref "BATT45") (pin "-") (pinfunction "-_-") (pintype "bidirectional"))
      (node (ref "BATT54") (pin "+") (pinfunction "+_+") (pintype "bidirectional"))
      (node (ref "BATT55") (pin "-") (pinfunction "-_-") (pintype "bidirectional"))
    )
    (net (code "33") (name "Net-(BATT45-Pad+)") (class "Default")
      (node (ref "BATT45") (pin "+") (pinfunction "+_+") (pintype "bidirectional"))
      (node (ref "BATT46") (pin "-") (pinfunction "-_-") (pintype "bidirectional"))
      (node (ref "BATT55") (pin "+") (pinfunction "+_+") (pintype "bidirectional"))
      (node (ref "BATT56") (pin "-") (pinfunction "-_-") (pintype "bidirectional"))
    )
    (net (code "34") (name "Net-(BATT46-Pad+)") (class "Default")
      (node (ref "BATT46") (pin "+") (pinfunction "+_+") (pintype "bidirectional"))
      (node (ref "BATT47") (pin "-") (pinfunction "-_-") (pintype "bidirectional"))
      (node (ref "BATT56") (pin "+") (pinfunction "+_+") (pintype "bidirectional"))
      (node (ref "BATT57") (pin "-") (pinfunction "-_-") (pintype "bidirectional"))
    )
    (net (code "35") (name "Net-(BATT47-Pad+)") (class "Default")
      (node (ref "BATT47") (pin "+") (pinfunction "+_+") (pintype "bidirectional"))
      (node (ref "BATT48") (pin "-") (pinfunction "-_-") (pintype "bidirectional"))
      (node (ref "BATT57") (pin "+") (pinfunction "+_+") (pintype "bidirectional"))
      (node (ref "BATT58") (pin "-") (pinfunction "-_-") (pintype "bidirectional"))
    )
    (net (code "36") (name "Net-(BATT48-Pad+)") (class "Default")
      (node (ref "BATT48") (pin "+") (pinfunction "+_+") (pintype "bidirectional"))
      (node (ref "BATT49") (pin "-") (pinfunction "-_-") (pintype "bidirectional"))
      (node (ref "BATT58") (pin "+") (pinfunction "+_+") (pintype "bidirectional"))
      (node (ref "BATT59") (pin "-") (pinfunction "-_-") (pintype "bidirectional"))
    )
    (net (code "37") (name "Net-(BATT49-Pad+)") (class "Default")
      (node (ref "BATT49") (pin "+") (pinfunction "+_+") (pintype "bidirectional"))
      (node (ref "BATT50") (pin "-") (pinfunction "-_-") (pintype "bidirectional"))
      (node (ref "BATT59") (pin "+") (pinfunction "+_+") (pintype "bidirectional"))
      (node (ref "BATT60") (pin "-") (pinfunction "-_-") (pintype "bidirectional"))
    )
    (net (code "38") (name "Net-(BATT50-Pad+)") (class "Default")
      (node (ref "BATT50") (pin "+") (pinfunction "+_+") (pintype "bidirectional"))
      (node (ref "BATT60") (pin "+") (pinfunction "+_+") (pintype "bidirectional"))
      (node (ref "MP2") (pin "1") (pinfunction "1_1") (pintype "passive"))
    )
    (net (code "39") (name "Net-(BATT61-Pad+)") (class "Default")
      (node (ref "BATT61") (pin "+") (pinfunction "+_+") (pintype "bidirectional"))
      (node (ref "BATT62") (pin "-") (pinfunction "-_-") (pintype "bidirectional"))
      (node (ref "BATT71") (pin "+") (pinfunction "+_+") (pintype "bidirectional"))
      (node (ref "BATT72") (pin "-") (pinfunction "-_-") (pintype "bidirectional"))
    )
    (net (code "40") (name "Net-(BATT61-Pad-)") (class "Default")
      (node (ref "BATT61") (pin "-") (pinfunction "-_-") (pintype "bidirectional"))
      (node (ref "BATT71") (pin "-") (pinfunction "-_-") (pintype "bidirectional"))
      (node (ref "MP3") (pin "1") (pinfunction "1_1") (pintype "passive"))
    )
    (net (code "41") (name "Net-(BATT62-Pad+)") (class "Default")
      (node (ref "BATT62") (pin "+") (pinfunction "+_+") (pintype "bidirectional"))
      (node (ref "BATT63") (pin "-") (pinfunction "-_-") (pintype "bidirectional"))
      (node (ref "BATT72") (pin "+") (pinfunction "+_+") (pintype "bidirectional"))
      (node (ref "BATT73") (pin "-") (pinfunction "-_-") (pintype "bidirectional"))
    )
    (net (code "42") (name "Net-(BATT63-Pad+)") (class "Default")
      (node (ref "BATT63") (pin "+") (pinfunction "+_+") (pintype "bidirectional"))
      (node (ref "BATT64") (pin "-") (pinfunction "-_-") (pintype "bidirectional"))
      (node (ref "BATT73") (pin "+") (pinfunction "+_+") (pintype "bidirectional"))
      (node (ref "BATT74") (pin "-") (pinfunction "-_-") (pintype "bidirectional"))
    )
    (net (code "43") (name "Net-(BATT64-Pad+)") (class "Default")
      (node (ref "BATT64") (pin "+") (pinfunction "+_+") (pintype "bidirectional"))
      (node (ref "BATT65") (pin "-") (pinfunction "-_-") (pintype "bidirectional"))
      (node (ref "BATT74") (pin "+") (pinfunction "+_+") (pintype "bidirectional"))
      (node (ref "BATT75") (pin "-") (pinfunction "-_-") (pintype "bidirectional"))
    )
    (net (code "44") (name "Net-(BATT65-Pad+)") (class "Default")
      (node (ref "BATT65") (pin "+") (pinfunction "+_+") (pintype "bidirectional"))
      (node (ref "BATT66") (pin "-") (pinfunction "-_-") (pintype "bidirectional"))
      (node (ref "BATT75") (pin "+") (pinfunction "+_+") (pintype "bidirectional"))
      (node (ref "BATT76") (pin "-") (pinfunction "-_-") (pintype "bidirectional"))
    )
    (net (code "45") (name "Net-(BATT66-Pad+)") (class "Default")
      (node (ref "BATT66") (pin "+") (pinfunction "+_+") (pintype "bidirectional"))
      (node (ref "BATT67") (pin "-") (pinfunction "-_-") (pintype "bidirectional"))
      (node (ref "BATT76") (pin "+") (pinfunction "+_+") (pintype "bidirectional"))
      (node (ref "BATT77") (pin "-") (pinfunction "-_-") (pintype "bidirectional"))
    )
    (net (code "46") (name "Net-(BATT67-Pad+)") (class "Default")
      (node (ref "BATT67") (pin "+") (pinfunction "+_+") (pintype "bidirectional"))
      (node (ref "BATT68") (pin "-") (pinfunction "-_-") (pintype "bidirectional"))
      (node (ref "BATT77") (pin "+") (pinfunction "+_+") (pintype "bidirectional"))
      (node (ref "BATT78") (pin "-") (pinfunction "-_-") (pintype "bidirectional"))
    )
    (net (code "47") (name "Net-(BATT68-Pad+)") (class "Default")
      (node (ref "BATT68") (pin "+") (pinfunction "+_+") (pintype "bidirectional"))
      (node (ref "BATT69") (pin "-") (pinfunction "-_-") (pintype "bidirectional"))
      (node (ref "BATT78") (pin "+") (pinfunction "+_+") (pintype "bidirectional"))
      (node (ref "BATT79") (pin "-") (pinfunction "-_-") (pintype "bidirectional"))
    )
    (net (code "48") (name "Net-(BATT69-Pad+)") (class "Default")
      (node (ref "BATT69") (pin "+") (pinfunction "+_+") (pintype "bidirectional"))
      (node (ref "BATT70") (pin "-") (pinfunction "-_-") (pintype "bidirectional"))
      (node (ref "BATT79") (pin "+") (pinfunction "+_+") (pintype "bidirectional"))
      (node (ref "BATT80") (pin "-") (pinfunction "-_-") (pintype "bidirectional"))
    )
    (net (code "49") (name "Net-(BATT70-Pad+)") (class "Default")
      (node (ref "BATT70") (pin "+") (pinfunction "+_+") (pintype "bidirectional"))
      (node (ref "BATT80") (pin "+") (pinfunction "+_+") (pintype "bidirectional"))
      (node (ref "BATT81") (pin "-") (pinfunction "-_-") (pintype "bidirectional"))
      (node (ref "BATT91") (pin "-") (pinfunction "-_-") (pintype "bidirectional"))
    )
    (net (code "50") (name "Net-(BATT81-Pad+)") (class "Default")
      (node (ref "BATT81") (pin "+") (pinfunction "+_+") (pintype "bidirectional"))
      (node (ref "BATT82") (pin "-") (pinfunction "-_-") (pintype "bidirectional"))
      (node (ref "BATT91") (pin "+") (pinfunction "+_+") (pintype "bidirectional"))
      (node (ref "BATT92") (pin "-") (pinfunction "-_-") (pintype "bidirectional"))
    )
    (net (code "51") (name "Net-(BATT82-Pad+)") (class "Default")
      (node (ref "BATT82") (pin "+") (pinfunction "+_+") (pintype "bidirectional"))
      (node (ref "BATT83") (pin "-") (pinfunction "-_-") (pintype "bidirectional"))
      (node (ref "BATT92") (pin "+") (pinfunction "+_+") (pintype "bidirectional"))
      (node (ref "BATT93") (pin "-") (pinfunction "-_-") (pintype "bidirectional"))
    )
    (net (code "52") (name "Net-(BATT83-Pad+)") (class "Default")
      (node (ref "BATT83") (pin "+") (pinfunction "+_+") (pintype "bidirectional"))
      (node (ref "BATT84") (pin "-") (pinfunction "-_-") (pintype "bidirectional"))
      (node (ref "BATT93") (pin "+") (pinfunction "+_+") (pintype "bidirectional"))
      (node (ref "BATT94") (pin "-") (pinfunction "-_-") (pintype "bidirectional"))
    )
    (net (code "53") (name "Net-(BATT84-Pad+)") (class "Default")
      (node (ref "BATT84") (pin "+") (pinfunction "+_+") (pintype "bidirectional"))
      (node (ref "BATT85") (pin "-") (pinfunction "-_-") (pintype "bidirectional"))
      (node (ref "BATT94") (pin "+") (pinfunction "+_+") (pintype "bidirectional"))
      (node (ref "BATT95") (pin "-") (pinfunction "-_-") (pintype "bidirectional"))
    )
    (net (code "54") (name "Net-(BATT85-Pad+)") (class "Default")
      (node (ref "BATT85") (pin "+") (pinfunction "+_+") (pintype "bidirectional"))
      (node (ref "BATT86") (pin "-") (pinfunction "-_-") (pintype "bidirectional"))
      (node (ref "BATT95") (pin "+") (pinfunction "+_+") (pintype "bidirectional"))
      (node (ref "BATT96") (pin "-") (pinfunction "-_-") (pintype "bidirectional"))
    )
    (net (code "55") (name "Net-(BATT86-Pad+)") (class "Default")
      (node (ref "BATT86") (pin "+") (pinfunction "+_+") (pintype "bidirectional"))
      (node (ref "BATT87") (pin "-") (pinfunction "-_-") (pintype "bidirectional"))
      (node (ref "BATT96") (pin "+") (pinfunction "+_+") (pintype "bidirectional"))
      (node (ref "BATT97") (pin "-") (pinfunction "-_-") (pintype "bidirectional"))
    )
    (net (code "56") (name "Net-(BATT87-Pad+)") (class "Default")
      (node (ref "BATT87") (pin "+") (pinfunction "+_+") (pintype "bidirectional"))
      (node (ref "BATT88") (pin "-") (pinfunction "-_-") (pintype "bidirectional"))
      (node (ref "BATT97") (pin "+") (pinfunction "+_+") (pintype "bidirectional"))
      (node (ref "BATT98") (pin "-") (pinfunction "-_-") (pintype "bidirectional"))
    )
    (net (code "57") (name "Net-(BATT88-Pad+)") (class "Default")
      (node (ref "BATT88") (pin "+") (pinfunction "+_+") (pintype "bidirectional"))
      (node (ref "BATT89") (pin "-") (pinfunction "-_-") (pintype "bidirectional"))
      (node (ref "BATT98") (pin "+") (pinfunction "+_+") (pintype "bidirectional"))
      (node (ref "BATT99") (pin "-") (pinfunction "-_-") (pintype "bidirectional"))
    )
    (net (code "58") (name "Net-(BATT100-Pad+)") (class "Default")
      (node (ref "BATT100") (pin "+") (pinfunction "+_+") (pintype "bidirectional"))
      (node (ref "BATT90") (pin "+") (pinfunction "+_+") (pintype "bidirectional"))
      (node (ref "MP4") (pin "1") (pinfunction "1_1") (pintype "passive"))
    )
    (net (code "59") (name "Net-(BATT100-Pad-)") (class "Default")
      (node (ref "BATT100") (pin "-") (pinfunction "-_-") (pintype "bidirectional"))
      (node (ref "BATT89") (pin "+") (pinfunction "+_+") (pintype "bidirectional"))
      (node (ref "BATT90") (pin "-") (pinfunction "-_-") (pintype "bidirectional"))
      (node (ref "BATT99") (pin "+") (pinfunction "+_+") (pintype "bidirectional"))
    )
    (net (code "60") (name "Net-(BATT101-Pad+)") (class "Default")
      (node (ref "BATT101") (pin "+") (pinfunction "+_+") (pintype "bidirectional"))
      (node (ref "BATT102") (pin "-") (pinfunction "-_-") (pintype "bidirectional"))
      (node (ref "BATT111") (pin "+") (pinfunction "+_+") (pintype "bidirectional"))
      (node (ref "BATT112") (pin "-") (pinfunction "-_-") (pintype "bidirectional"))
    )
    (net (code "61") (name "Net-(BATT101-Pad-)") (class "Default")
      (node (ref "BATT101") (pin "-") (pinfunction "-_-") (pintype "bidirectional"))
      (node (ref "BATT111") (pin "-") (pinfunction "-_-") (pintype "bidirectional"))
      (node (ref "MP5") (pin "1") (pinfunction "1_1") (pintype "passive"))
    )
    (net (code "62") (name "Net-(BATT102-Pad+)") (class "Default")
      (node (ref "BATT102") (pin "+") (pinfunction "+_+") (pintype "bidirectional"))
      (node (ref "BATT103") (pin "-") (pinfunction "-_-") (pintype "bidirectional"))
      (node (ref "BATT112") (pin "+") (pinfunction "+_+") (pintype "bidirectional"))
      (node (ref "BATT113") (pin "-") (pinfunction "-_-") (pintype "bidirectional"))
    )
    (net (code "63") (name "Net-(BATT103-Pad+)") (class "Default")
      (node (ref "BATT103") (pin "+") (pinfunction "+_+") (pintype "bidirectional"))
      (node (ref "BATT104") (pin "-") (pinfunction "-_-") (pintype "bidirectional"))
      (node (ref "BATT113") (pin "+") (pinfunction "+_+") (pintype "bidirectional"))
      (node (ref "BATT114") (pin "-") (pinfunction "-_-") (pintype "bidirectional"))
    )
    (net (code "64") (name "Net-(BATT104-Pad+)") (class "Default")
      (node (ref "BATT104") (pin "+") (pinfunction "+_+") (pintype "bidirectional"))
      (node (ref "BATT105") (pin "-") (pinfunction "-_-") (pintype "bidirectional"))
      (node (ref "BATT114") (pin "+") (pinfunction "+_+") (pintype "bidirectional"))
      (node (ref "BATT115") (pin "-") (pinfunction "-_-") (pintype "bidirectional"))
    )
    (net (code "65") (name "Net-(BATT105-Pad+)") (class "Default")
      (node (ref "BATT105") (pin "+") (pinfunction "+_+") (pintype "bidirectional"))
      (node (ref "BATT106") (pin "-") (pinfunction "-_-") (pintype "bidirectional"))
      (node (ref "BATT115") (pin "+") (pinfunction "+_+") (pintype "bidirectional"))
      (node (ref "BATT116") (pin "-") (pinfunction "-_-") (pintype "bidirectional"))
    )
    (net (code "66") (name "Net-(BATT106-Pad+)") (class "Default")
      (node (ref "BATT106") (pin "+") (pinfunction "+_+") (pintype "bidirectional"))
      (node (ref "BATT107") (pin "-") (pinfunction "-_-") (pintype "bidirectional"))
      (node (ref "BATT116") (pin "+") (pinfunction "+_+") (pintype "bidirectional"))
      (node (ref "BATT117") (pin "-") (pinfunction "-_-") (pintype "bidirectional"))
    )
    (net (code "67") (name "Net-(BATT107-Pad+)") (class "Default")
      (node (ref "BATT107") (pin "+") (pinfunction "+_+") (pintype "bidirectional"))
      (node (ref "BATT108") (pin "-") (pinfunction "-_-") (pintype "bidirectional"))
      (node (ref "BATT117") (pin "+") (pinfunction "+_+") (pintype "bidirectional"))
      (node (ref "BATT118") (pin "-") (pinfunction "-_-") (pintype "bidirectional"))
    )
    (net (code "68") (name "Net-(BATT108-Pad+)") (class "Default")
      (node (ref "BATT108") (pin "+") (pinfunction "+_+") (pintype "bidirectional"))
      (node (ref "BATT109") (pin "-") (pinfunction "-_-") (pintype "bidirectional"))
      (node (ref "BATT118") (pin "+") (pinfunction "+_+") (pintype "bidirectional"))
      (node (ref "BATT119") (pin "-") (pinfunction "-_-") (pintype "bidirectional"))
    )
    (net (code "69") (name "Net-(BATT109-Pad+)") (class "Default")
      (node (ref "BATT109") (pin "+") (pinfunction "+_+") (pintype "bidirectional"))
      (node (ref "BATT110") (pin "-") (pinfunction "-_-") (pintype "bidirectional"))
      (node (ref "BATT119") (pin "+") (pinfunction "+_+") (pintype "bidirectional"))
      (node (ref "BATT120") (pin "-") (pinfunction "-_-") (pintype "bidirectional"))
    )
    (net (code "70") (name "Net-(BATT110-Pad+)") (class "Default")
      (node (ref "BATT110") (pin "+") (pinfunction "+_+") (pintype "bidirectional"))
      (node (ref "BATT120") (pin "+") (pinfunction "+_+") (pintype "bidirectional"))
      (node (ref "BATT121") (pin "-") (pinfunction "-_-") (pintype "bidirectional"))
      (node (ref "BATT131") (pin "-") (pinfunction "-_-") (pintype "bidirectional"))
    )
    (net (code "71") (name "Net-(BATT121-Pad+)") (class "Default")
      (node (ref "BATT121") (pin "+") (pinfunction "+_+") (pintype "bidirectional"))
      (node (ref "BATT122") (pin "-") (pinfunction "-_-") (pintype "bidirectional"))
      (node (ref "BATT131") (pin "+") (pinfunction "+_+") (pintype "bidirectional"))
      (node (ref "BATT132") (pin "-") (pinfunction "-_-") (pintype "bidirectional"))
    )
    (net (code "72") (name "Net-(BATT122-Pad+)") (class "Default")
      (node (ref "BATT122") (pin "+") (pinfunction "+_+") (pintype "bidirectional"))
      (node (ref "BATT123") (pin "-") (pinfunction "-_-") (pintype "bidirectional"))
      (node (ref "BATT132") (pin "+") (pinfunction "+_+") (pintype "bidirectional"))
      (node (ref "BATT133") (pin "-") (pinfunction "-_-") (pintype "bidirectional"))
    )
    (net (code "73") (name "Net-(BATT123-Pad+)") (class "Default")
      (node (ref "BATT123") (pin "+") (pinfunction "+_+") (pintype "bidirectional"))
      (node (ref "BATT124") (pin "-") (pinfunction "-_-") (pintype "bidirectional"))
      (node (ref "BATT133") (pin "+") (pinfunction "+_+") (pintype "bidirectional"))
      (node (ref "BATT134") (pin "-") (pinfunction "-_-") (pintype "bidirectional"))
    )
    (net (code "74") (name "Net-(BATT124-Pad+)") (class "Default")
      (node (ref "BATT124") (pin "+") (pinfunction "+_+") (pintype "bidirectional"))
      (node (ref "BATT125") (pin "-") (pinfunction "-_-") (pintype "bidirectional"))
      (node (ref "BATT134") (pin "+") (pinfunction "+_+") (pintype "bidirectional"))
      (node (ref "BATT135") (pin "-") (pinfunction "-_-") (pintype "bidirectional"))
    )
    (net (code "75") (name "Net-(BATT125-Pad+)") (class "Default")
      (node (ref "BATT125") (pin "+") (pinfunction "+_+") (pintype "bidirectional"))
      (node (ref "BATT126") (pin "-") (pinfunction "-_-") (pintype "bidirectional"))
      (node (ref "BATT135") (pin "+") (pinfunction "+_+") (pintype "bidirectional"))
      (node (ref "BATT136") (pin "-") (pinfunction "-_-") (pintype "bidirectional"))
    )
    (net (code "76") (name "Net-(BATT126-Pad+)") (class "Default")
      (node (ref "BATT126") (pin "+") (pinfunction "+_+") (pintype "bidirectional"))
      (node (ref "BATT127") (pin "-") (pinfunction "-_-") (pintype "bidirectional"))
      (node (ref "BATT136") (pin "+") (pinfunction "+_+") (pintype "bidirectional"))
      (node (ref "BATT137") (pin "-") (pinfunction "-_-") (pintype "bidirectional"))
    )
    (net (code "77") (name "Net-(BATT127-Pad+)") (class "Default")
      (node (ref "BATT127") (pin "+") (pinfunction "+_+") (pintype "bidirectional"))
      (node (ref "BATT128") (pin "-") (pinfunction "-_-") (pintype "bidirectional"))
      (node (ref "BATT137") (pin "+") (pinfunction "+_+") (pintype "bidirectional"))
      (node (ref "BATT138") (pin "-") (pinfunction "-_-") (pintype "bidirectional"))
    )
    (net (code "78") (name "Net-(BATT128-Pad+)") (class "Default")
      (node (ref "BATT128") (pin "+") (pinfunction "+_+") (pintype "bidirectional"))
      (node (ref "BATT129") (pin "-") (pinfunction "-_-") (pintype "bidirectional"))
      (node (ref "BATT138") (pin "+") (pinfunction "+_+") (pintype "bidirectional"))
      (node (ref "BATT139") (pin "-") (pinfunction "-_-") (pintype "bidirectional"))
    )
    (net (code "79") (name "Net-(BATT129-Pad+)") (class "Default")
      (node (ref "BATT129") (pin "+") (pinfunction "+_+") (pintype "bidirectional"))
      (node (ref "BATT130") (pin "-") (pinfunction "-_-") (pintype "bidirectional"))
      (node (ref "BATT139") (pin "+") (pinfunction "+_+") (pintype "bidirectional"))
      (node (ref "BATT140") (pin "-") (pinfunction "-_-") (pintype "bidirectional"))
    )
    (net (code "80") (name "Net-(BATT130-Pad+)") (class "Default")
      (node (ref "BATT130") (pin "+") (pinfunction "+_+") (pintype "bidirectional"))
      (node (ref "BATT140") (pin "+") (pinfunction "+_+") (pintype "bidirectional"))
      (node (ref "MP6") (pin "1") (pinfunction "1_1") (pintype "passive"))
    )
    (net (code "81") (name "Net-(BATT141-Pad+)") (class "Default")
      (node (ref "BATT141") (pin "+") (pinfunction "+_+") (pintype "bidirectional"))
      (node (ref "BATT142") (pin "-") (pinfunction "-_-") (pintype "bidirectional"))
      (node (ref "BATT151") (pin "+") (pinfunction "+_+") (pintype "bidirectional"))
      (node (ref "BATT152") (pin "-") (pinfunction "-_-") (pintype "bidirectional"))
    )
    (net (code "82") (name "Net-(BATT141-Pad-)") (class "Default")
      (node (ref "BATT141") (pin "-") (pinfunction "-_-") (pintype "bidirectional"))
      (node (ref "BATT151") (pin "-") (pinfunction "-_-") (pintype "bidirectional"))
      (node (ref "MP7") (pin "1") (pinfunction "1_1") (pintype "passive"))
    )
    (net (code "83") (name "Net-(BATT142-Pad+)") (class "Default")
      (node (ref "BATT142") (pin "+") (pinfunction "+_+") (pintype "bidirectional"))
      (node (ref "BATT143") (pin "-") (pinfunction "-_-") (pintype "bidirectional"))
      (node (ref "BATT152") (pin "+") (pinfunction "+_+") (pintype "bidirectional"))
      (node (ref "BATT153") (pin "-") (pinfunction "-_-") (pintype "bidirectional"))
    )
    (net (code "84") (name "Net-(BATT143-Pad+)") (class "Default")
      (node (ref "BATT143") (pin "+") (pinfunction "+_+") (pintype "bidirectional"))
      (node (ref "BATT144") (pin "-") (pinfunction "-_-") (pintype "bidirectional"))
      (node (ref "BATT153") (pin "+") (pinfunction "+_+") (pintype "bidirectional"))
      (node (ref "BATT154") (pin "-") (pinfunction "-_-") (pintype "bidirectional"))
    )
    (net (code "85") (name "Net-(BATT144-Pad+)") (class "Default")
      (node (ref "BATT144") (pin "+") (pinfunction "+_+") (pintype "bidirectional"))
      (node (ref "BATT145") (pin "-") (pinfunction "-_-") (pintype "bidirectional"))
      (node (ref "BATT154") (pin "+") (pinfunction "+_+") (pintype "bidirectional"))
      (node (ref "BATT155") (pin "-") (pinfunction "-_-") (pintype "bidirectional"))
    )
    (net (code "86") (name "Net-(BATT145-Pad+)") (class "Default")
      (node (ref "BATT145") (pin "+") (pinfunction "+_+") (pintype "bidirectional"))
      (node (ref "BATT146") (pin "-") (pinfunction "-_-") (pintype "bidirectional"))
      (node (ref "BATT155") (pin "+") (pinfunction "+_+") (pintype "bidirectional"))
      (node (ref "BATT156") (pin "-") (pinfunction "-_-") (pintype "bidirectional"))
    )
    (net (code "87") (name "Net-(BATT146-Pad+)") (class "Default")
      (node (ref "BATT146") (pin "+") (pinfunction "+_+") (pintype "bidirectional"))
      (node (ref "BATT147") (pin "-") (pinfunction "-_-") (pintype "bidirectional"))
      (node (ref "BATT156") (pin "+") (pinfunction "+_+") (pintype "bidirectional"))
      (node (ref "BATT157") (pin "-") (pinfunction "-_-") (pintype "bidirectional"))
    )
    (net (code "88") (name "Net-(BATT147-Pad+)") (class "Default")
      (node (ref "BATT147") (pin "+") (pinfunction "+_+") (pintype "bidirectional"))
      (node (ref "BATT148") (pin "-") (pinfunction "-_-") (pintype "bidirectional"))
      (node (ref "BATT157") (pin "+") (pinfunction "+_+") (pintype "bidirectional"))
      (node (ref "BATT158") (pin "-") (pinfunction "-_-") (pintype "bidirectional"))
    )
    (net (code "89") (name "Net-(BATT148-Pad+)") (class "Default")
      (node (ref "BATT148") (pin "+") (pinfunction "+_+") (pintype "bidirectional"))
      (node (ref "BATT149") (pin "-") (pinfunction "-_-") (pintype "bidirectional"))
      (node (ref "BATT158") (pin "+") (pinfunction "+_+") (pintype "bidirectional"))
      (node (ref "BATT159") (pin "-") (pinfunction "-_-") (pintype "bidirectional"))
    )
    (net (code "90") (name "Net-(BATT149-Pad+)") (class "Default")
      (node (ref "BATT149") (pin "+") (pinfunction "+_+") (pintype "bidirectional"))
      (node (ref "BATT150") (pin "-") (pinfunction "-_-") (pintype "bidirectional"))
      (node (ref "BATT159") (pin "+") (pinfunction "+_+") (pintype "bidirectional"))
      (node (ref "BATT160") (pin "-") (pinfunction "-_-") (pintype "bidirectional"))
    )
    (net (code "91") (name "Net-(BATT150-Pad+)") (class "Default")
      (node (ref "BATT150") (pin "+") (pinfunction "+_+") (pintype "bidirectional"))
      (node (ref "BATT160") (pin "+") (pinfunction "+_+") (pintype "bidirectional"))
      (node (ref "MP8") (pin "1") (pinfunction "1_1") (pintype "passive"))
    )
    (net (code "92") (name "Net-(BMS1-Pad-)") (class "Default")
      (node (ref "BMS1") (pin "-") (pinfunction "-_-") (pintype "passive"))
      (node (ref "BMS2") (pin "+") (pinfunction "+_+") (pintype "passive"))
    )
    (net (code "93") (name "Net-(BMS2-Pad-)") (class "Default")
      (node (ref "BMS2") (pin "-") (pinfunction "-_-") (pintype "passive"))
      (node (ref "BMS3") (pin "+") (pinfunction "+_+") (pintype "passive"))
    )
    (net (code "94") (name "Net-(BMS3-Pad-)") (class "Default")
      (node (ref "BMS3") (pin "-") (pinfunction "-_-") (pintype "passive"))
      (node (ref "BMS4") (pin "+") (pinfunction "+_+") (pintype "passive"))
    )
    (net (code "95") (name "Net-(BMS4-Pad-)") (class "Default")
      (node (ref "BMS4") (pin "-") (pinfunction "-_-") (pintype "passive"))
      (node (ref "BMS5") (pin "+") (pinfunction "+_+") (pintype "passive"))
    )
    (net (code "96") (name "Net-(BMS5-Pad-)") (class "Default")
      (node (ref "BMS5") (pin "-") (pinfunction "-_-") (pintype "passive"))
      (node (ref "BMS6") (pin "+") (pinfunction "+_+") (pintype "passive"))
    )
    (net (code "97") (name "Net-(BMS6-Pad-)") (class "Default")
      (node (ref "BMS6") (pin "-") (pinfunction "-_-") (pintype "passive"))
      (node (ref "BMS7") (pin "+") (pinfunction "+_+") (pintype "passive"))
    )
    (net (code "98") (name "Net-(BMS8-Pad-)") (class "Default")
      (node (ref "BMS8") (pin "-") (pinfunction "-_-") (pintype "passive"))
      (node (ref "BMS9") (pin "+") (pinfunction "+_+") (pintype "passive"))
    )
    (net (code "99") (name "Net-(BMS10-Pad+)") (class "Default")
      (node (ref "BMS10") (pin "+") (pinfunction "+_+") (pintype "passive"))
      (node (ref "BMS9") (pin "-") (pinfunction "-_-") (pintype "passive"))
    )
    (net (code "100") (name "Net-(BMS10-Pad-)") (class "Default")
      (node (ref "BMS10") (pin "-") (pinfunction "-_-") (pintype "passive"))
      (node (ref "BMS11") (pin "+") (pinfunction "+_+") (pintype "passive"))
    )
    (net (code "101") (name "Net-(BMS11-Pad-)") (class "Default")
      (node (ref "BMS11") (pin "-") (pinfunction "-_-") (pintype "passive"))
      (node (ref "BMS12") (pin "+") (pinfunction "+_+") (pintype "passive"))
    )
    (net (code "102") (name "Net-(BMS12-Pad-)") (class "Default")
      (node (ref "BMS12") (pin "-") (pinfunction "-_-") (pintype "passive"))
      (node (ref "BMS13") (pin "+") (pinfunction "+_+") (pintype "passive"))
    )
    (net (code "103") (name "Net-(BMS13-Pad-)") (class "Default")
      (node (ref "BMS13") (pin "-") (pinfunction "-_-") (pintype "passive"))
      (node (ref "BMS14") (pin "+") (pinfunction "+_+") (pintype "passive"))
    )
    (net (code "104") (name "Net-(BMS16-Pad-)") (class "Default")
      (node (ref "BMS16") (pin "-") (pinfunction "-_-") (pintype "passive"))
      (node (ref "BMS17") (pin "+") (pinfunction "+_+") (pintype "passive"))
    )
    (net (code "105") (name "Net-(BMS17-Pad-)") (class "Default")
      (node (ref "BMS17") (pin "-") (pinfunction "-_-") (pintype "passive"))
      (node (ref "BMS18") (pin "+") (pinfunction "+_+") (pintype "passive"))
    )
    (net (code "106") (name "Net-(DISCHAGE-Pad1)") (class "Default")
      (node (ref "DISCHAGE") (pin "1") (pinfunction "1_1") (pintype "passive"))
      (node (ref "DISCHAGE1") (pin "2") (pinfunction "2_2") (pintype "passive"))
    )
    (net (code "107") (name "Net-(DISCHAGE1-Pad1)") (class "Default")
      (node (ref "DISCHAGE1") (pin "1") (pinfunction "1_1") (pintype "passive"))
      (node (ref "DISCHAGE2") (pin "2") (pinfunction "2_2") (pintype "passive"))
    )
    (net (code "108") (name "Net-(JP1-1)") (class "Default")
      (node (ref "JP1") (pin "P$1") (pinfunction "1_P$1") (pintype "passive"))
      (node (ref "R1") (pin "2") (pinfunction "2_2") (pintype "passive"))
    )
    (net (code "109") (name "Net-(JP2-1)") (class "Default")
      (node (ref "JP2") (pin "P$1") (pinfunction "1_P$1") (pintype "passive"))
      (node (ref "R2") (pin "2") (pinfunction "2_2") (pintype "passive"))
    )
    (net (code "110") (name "Net-(K1B-P)") (class "Default")
      (node (ref "F1") (pin "1") (pinfunction "1_1") (pintype "passive"))
      (node (ref "K1") (pin "COM") (pinfunction "P_COM") (pintype "passive"))
    )
    (net (code "111") (name "Net-(K2B-O)") (class "Default")
      (node (ref "DISCHAGE") (pin "2") (pinfunction "2_2") (pintype "passive"))
      (node (ref "K2") (pin "NC") (pinfunction "O_NC") (pintype "passive"))
    )
    (net (code "112") (name "Net-(K2B-P)") (class "Default")
      (node (ref "K2") (pin "COM") (pinfunction "P_COM") (pintype "passive"))
      (node (ref "PRECHARGE") (pin "2") (pinfunction "2_2") (pintype "passive"))
    )
    (net (code "113") (name "Net-(K2B-S)") (class "Default")
      (node (ref "F3") (pin "1") (pinfunction "1_1") (pintype "passive"))
      (node (ref "K2") (pin "NO") (pinfunction "S_NO") (pintype "passive"))
    )
    (net (code "114") (name "Net-(K4B-P)") (class "Default")
      (node (ref "F2") (pin "1") (pinfunction "1_1") (pintype "passive"))
      (node (ref "K4") (pin "COM") (pinfunction "P_COM") (pintype "passive"))
    )
    (net (code "115") (name "PRE-CHARGE") (class "Default")
      (node (ref "K2") (pin "1") (pinfunction "1_1") (pintype "passive"))
      (node (ref "K3") (pin "1") (pinfunction "1_1") (pintype "passive"))
    )
    (net (code "116") (name "TS+\\") (class "Default")
      (node (ref "K1") (pin "NO") (pinfunction "S_NO") (pintype "passive"))
      (node (ref "K4") (pin "NO") (pinfunction "S_NO") (pintype "passive"))
      (node (ref "PRECHARGE") (pin "1") (pinfunction "1_1") (pintype "passive"))
      (node (ref "R1") (pin "1") (pinfunction "1_1") (pintype "passive"))
    )
    (net (code "117") (name "TS-") (class "Default")
      (node (ref "DISCHAGE2") (pin "1") (pinfunction "1_1") (pintype "passive"))
      (node (ref "K3") (pin "NO") (pinfunction "S_NO") (pintype "passive"))
      (node (ref "K5") (pin "NO") (pinfunction "S_NO") (pintype "passive"))
      (node (ref "R2") (pin "1") (pinfunction "1_1") (pintype "passive"))
    )
    (net (code "118") (name "unconnected-(BMS1-+-Pad+@1)") (class "Default")
      (node (ref "BMS1") (pin "+@1") (pinfunction "+_+@1") (pintype "passive"))
    )
    (net (code "119") (name "unconnected-(BMS2-+-Pad+@1)") (class "Default")
      (node (ref "BMS2") (pin "+@1") (pinfunction "+_+@1") (pintype "passive"))
    )
    (net (code "120") (name "unconnected-(BMS3-+-Pad+@1)") (class "Default")
      (node (ref "BMS3") (pin "+@1") (pinfunction "+_+@1") (pintype "passive"))
    )
    (net (code "121") (name "unconnected-(BMS4-+-Pad+@1)") (class "Default")
      (node (ref "BMS4") (pin "+@1") (pinfunction "+_+@1") (pintype "passive"))
    )
    (net (code "122") (name "unconnected-(BMS5-+-Pad+@1)") (class "Default")
      (node (ref "BMS5") (pin "+@1") (pinfunction "+_+@1") (pintype "passive"))
    )
    (net (code "123") (name "unconnected-(BMS6-+-Pad+@1)") (class "Default")
      (node (ref "BMS6") (pin "+@1") (pinfunction "+_+@1") (pintype "passive"))
    )
    (net (code "124") (name "unconnected-(BMS7-+-Pad+@1)") (class "Default")
      (node (ref "BMS7") (pin "+@1") (pinfunction "+_+@1") (pintype "passive"))
    )
    (net (code "125") (name "unconnected-(BMS8-+-Pad+@1)") (class "Default")
      (node (ref "BMS8") (pin "+@1") (pinfunction "+_+@1") (pintype "passive"))
    )
    (net (code "126") (name "unconnected-(BMS9-+-Pad+@1)") (class "Default")
      (node (ref "BMS9") (pin "+@1") (pinfunction "+_+@1") (pintype "passive"))
    )
    (net (code "127") (name "unconnected-(BMS10-+-Pad+@1)") (class "Default")
      (node (ref "BMS10") (pin "+@1") (pinfunction "+_+@1") (pintype "passive"))
    )
    (net (code "128") (name "unconnected-(BMS11-+-Pad+@1)") (class "Default")
      (node (ref "BMS11") (pin "+@1") (pinfunction "+_+@1") (pintype "passive"))
    )
    (net (code "129") (name "unconnected-(BMS12-+-Pad+@1)") (class "Default")
      (node (ref "BMS12") (pin "+@1") (pinfunction "+_+@1") (pintype "passive"))
    )
    (net (code "130") (name "unconnected-(BMS13-+-Pad+@1)") (class "Default")
      (node (ref "BMS13") (pin "+@1") (pinfunction "+_+@1") (pintype "passive"))
    )
    (net (code "131") (name "unconnected-(BMS14-+-Pad+@1)") (class "Default")
      (node (ref "BMS14") (pin "+@1") (pinfunction "+_+@1") (pintype "passive"))
    )
    (net (code "132") (name "unconnected-(BMS15-+-Pad+@1)") (class "Default")
      (node (ref "BMS15") (pin "+@1") (pinfunction "+_+@1") (pintype "passive"))
    )
    (net (code "133") (name "unconnected-(BMS15-Pad+)") (class "Default")
      (node (ref "BMS15") (pin "+") (pinfunction "+_+") (pintype "passive"))
    )
    (net (code "134") (name "unconnected-(BMS15-Pad-)") (class "Default")
      (node (ref "BMS15") (pin "-") (pinfunction "-_-") (pintype "passive"))
    )
    (net (code "135") (name "unconnected-(BMS16-+-Pad+@1)") (class "Default")
      (node (ref "BMS16") (pin "+@1") (pinfunction "+_+@1") (pintype "passive"))
    )
    (net (code "136") (name "unconnected-(BMS16-Pad+)") (class "Default")
      (node (ref "BMS16") (pin "+") (pinfunction "+_+") (pintype "passive"))
    )
    (net (code "137") (name "unconnected-(BMS17-+-Pad+@1)") (class "Default")
      (node (ref "BMS17") (pin "+@1") (pinfunction "+_+@1") (pintype "passive"))
    )
    (net (code "138") (name "unconnected-(BMS18-+-Pad+@1)") (class "Default")
      (node (ref "BMS18") (pin "+@1") (pinfunction "+_+@1") (pintype "passive"))
    )
    (net (code "139") (name "unconnected-(BMS18-Pad-)") (class "Default")
      (node (ref "BMS18") (pin "-") (pinfunction "-_-") (pintype "passive"))
    )
  )
)
